# NAVIGATION_-_MCU.net
KiCad netlist of a schematic drawn in Altium Designer
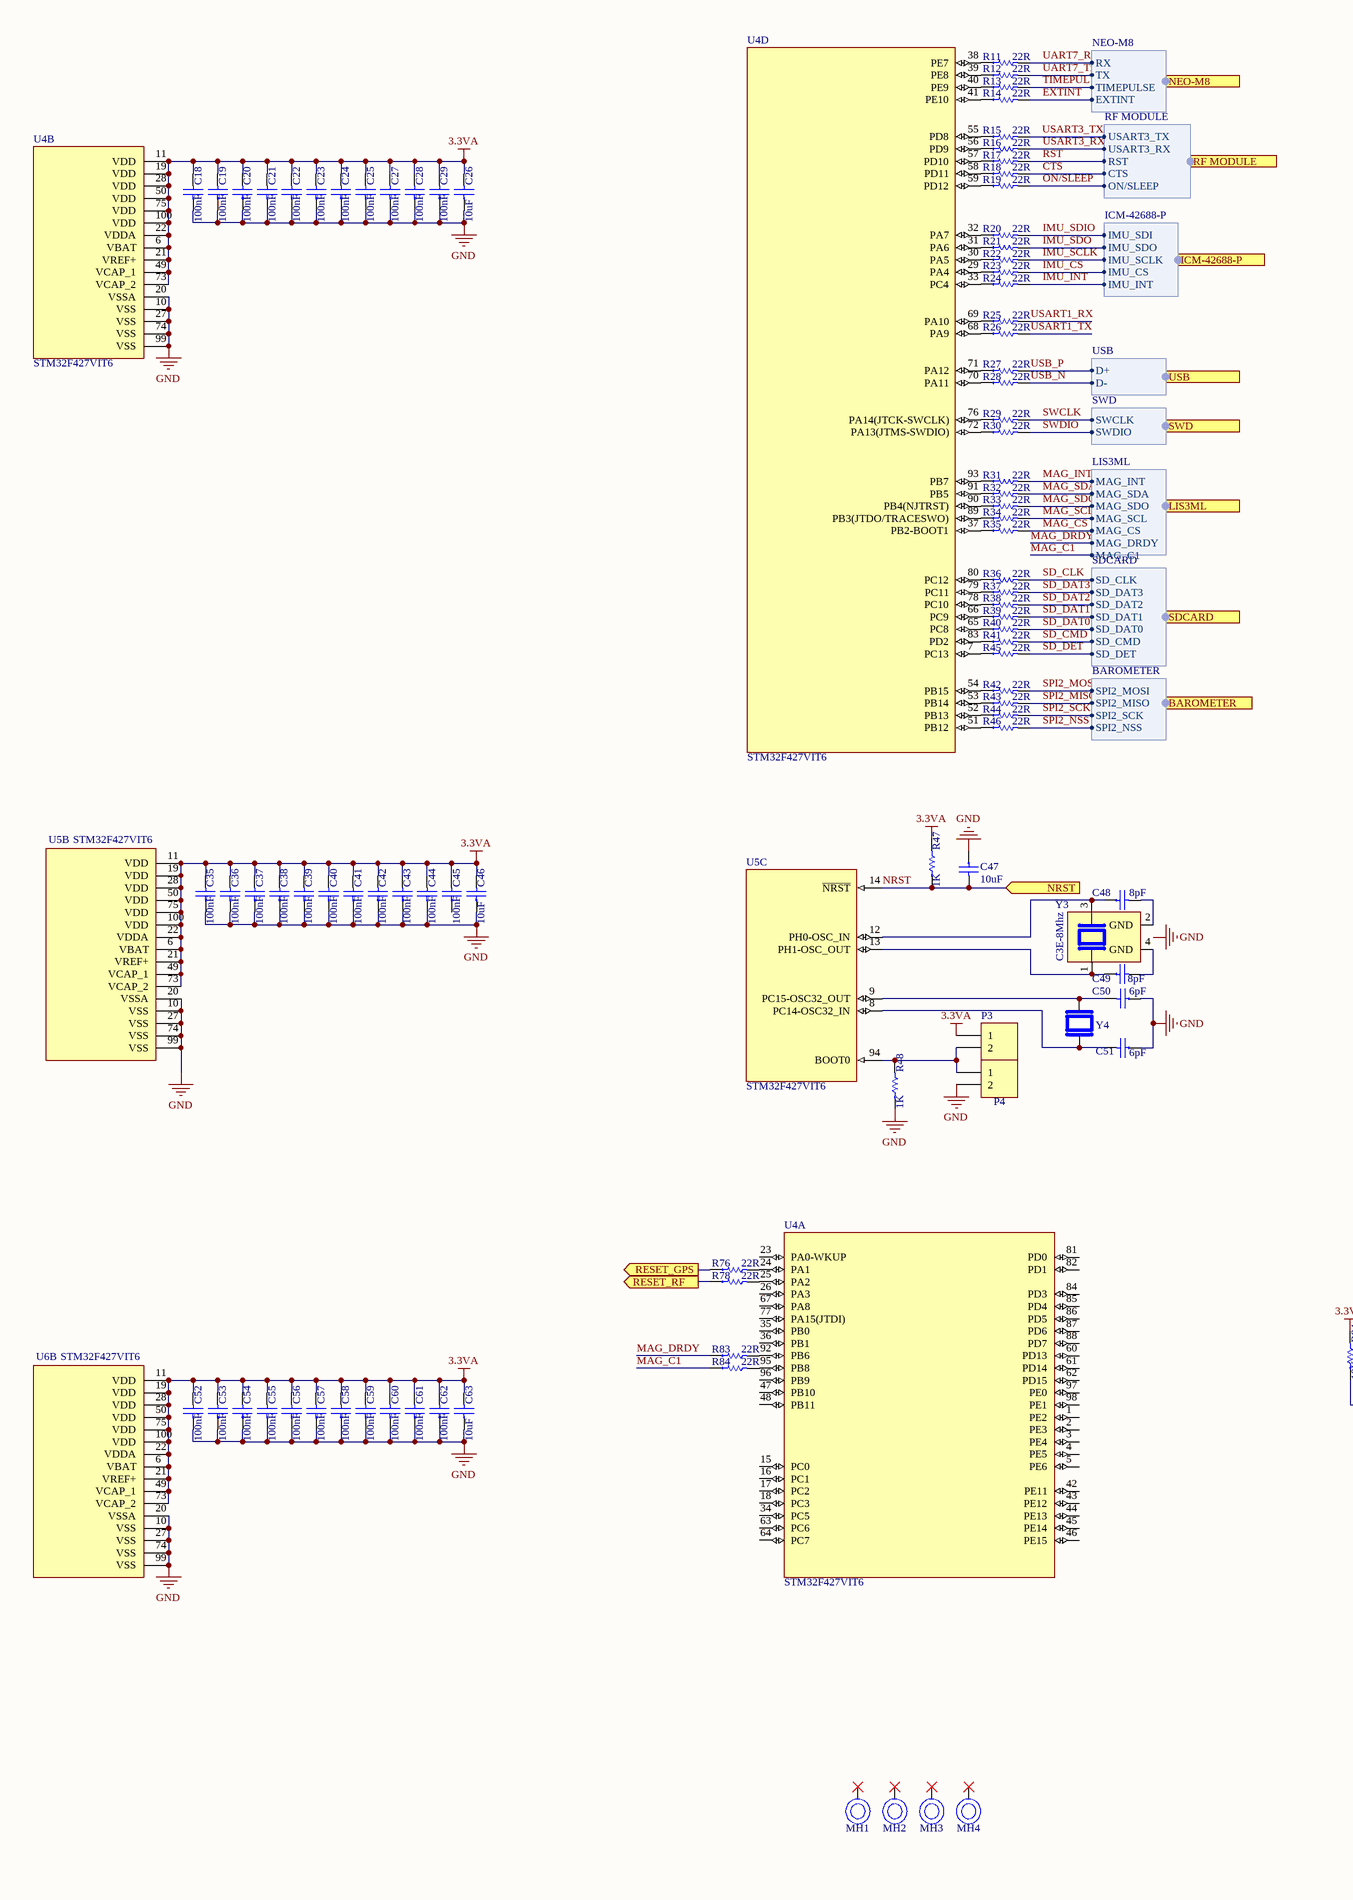
[diagram p0: NAVIGATION - MCU.SchDoc, left]
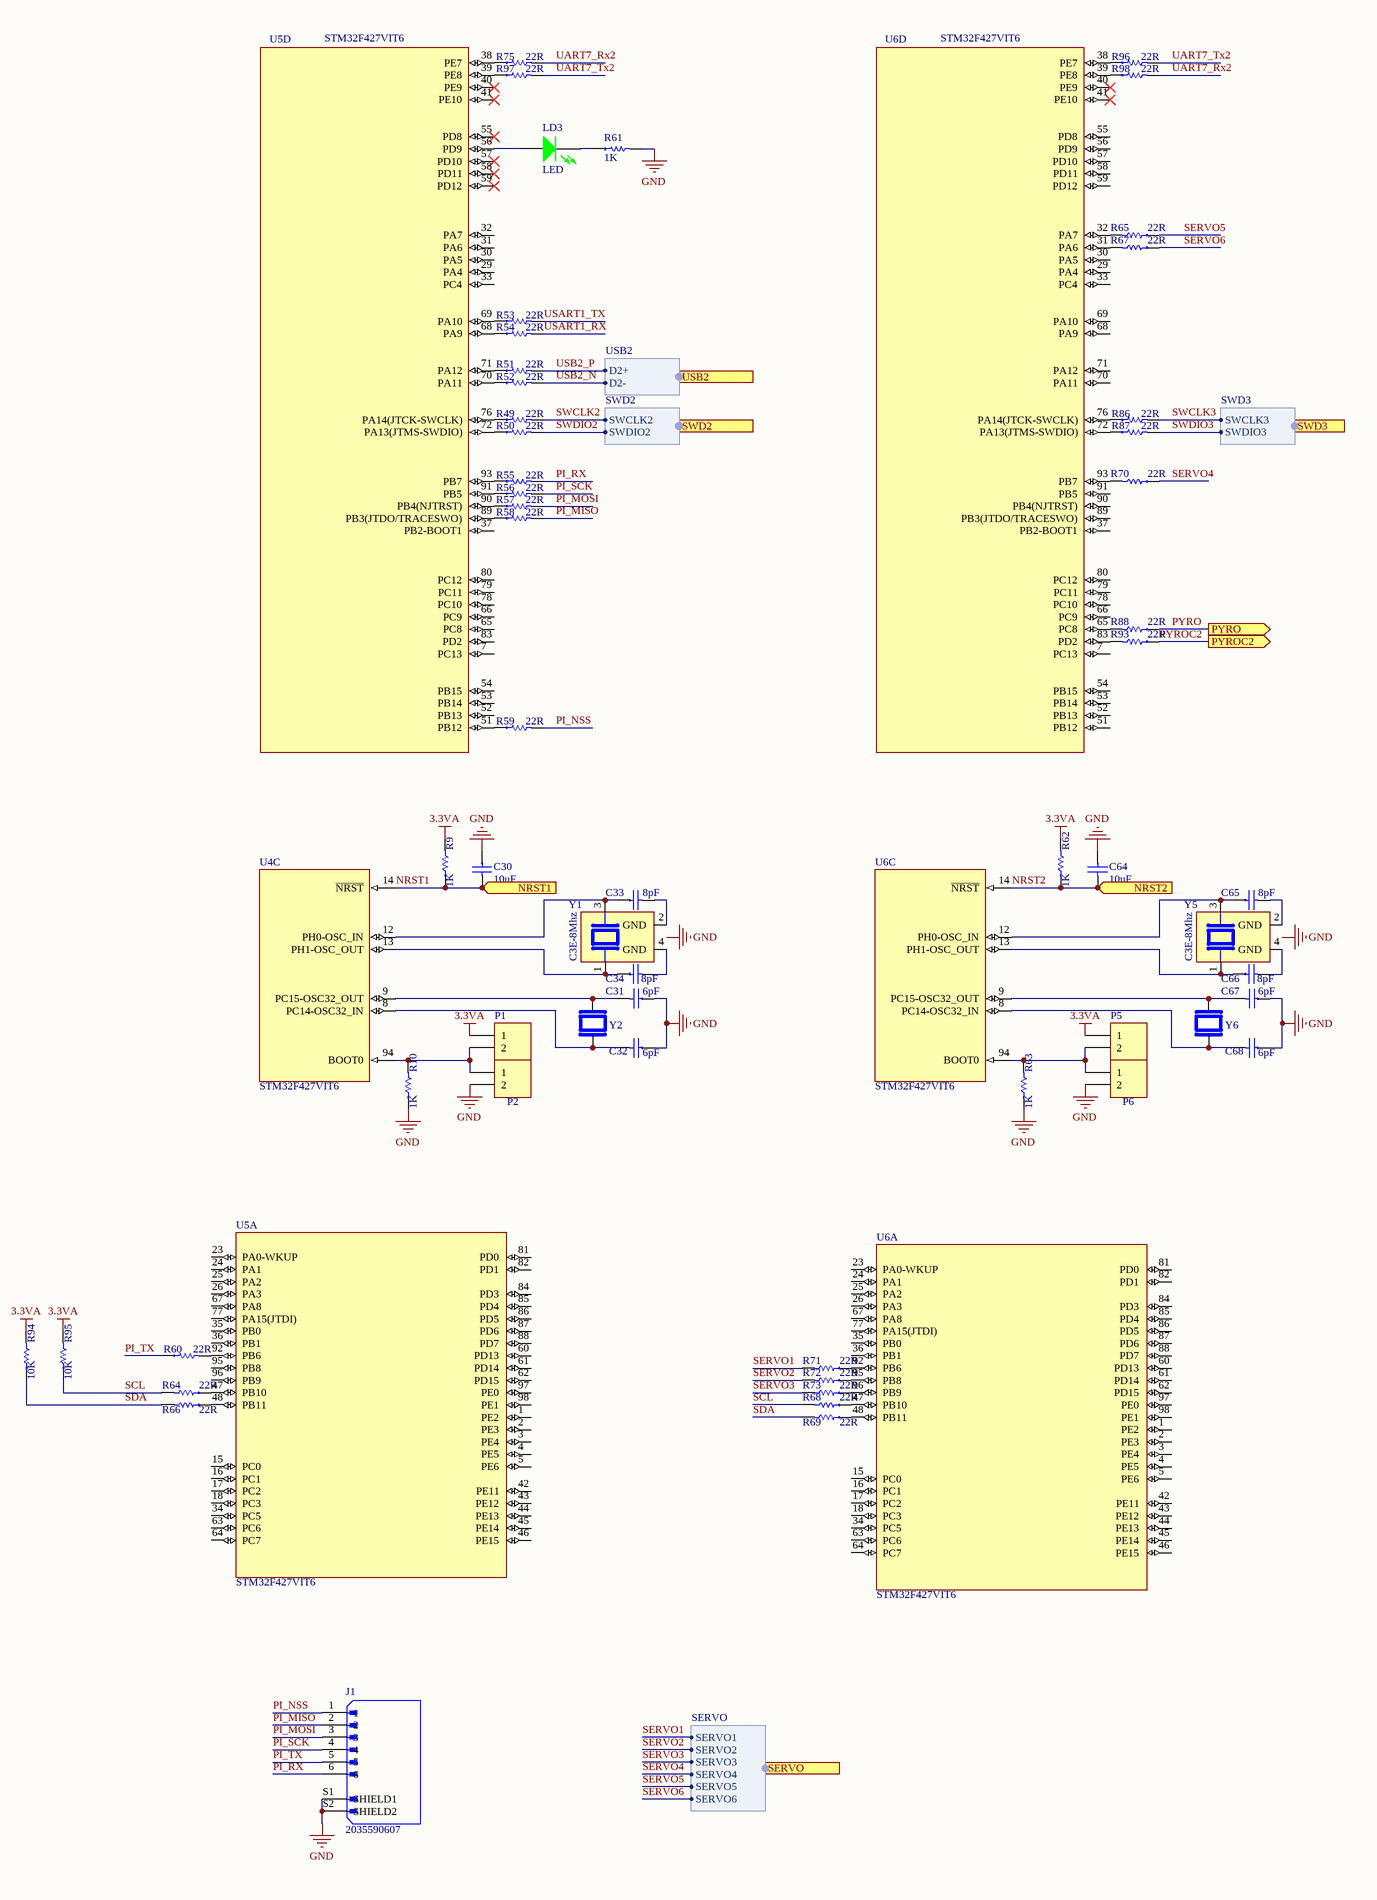
[diagram p1: NAVIGATION - MCU.SchDoc, right]

(export (version "E")
  (design (tool "Eeschema 10.0.6"))
  (components
    (comp (ref "C18")
      (value "100nF")
      (footprint "CAP-CER0402-0.5H")
      (description "CAP CER 100nF 10% 50V X7R 0402 SMD")
      (libsource (lib "2502-GMQLITE-MAIN") (part "CAPCER0013 100nF 10% 50V X7R 0402 SMD"))
    )
    (comp (ref "C19")
      (value "100nF")
      (footprint "CAP-CER0402-0.5H")
      (description "CAP CER 100nF 10% 50V X7R 0402 SMD")
      (libsource (lib "2502-GMQLITE-MAIN") (part "CAPCER0013 100nF 10% 50V X7R 0402 SMD"))
    )
    (comp (ref "C20")
      (value "100nF")
      (footprint "CAP-CER0402-0.5H")
      (description "CAP CER 100nF 10% 50V X7R 0402 SMD")
      (libsource (lib "2502-GMQLITE-MAIN") (part "CAPCER0013 100nF 10% 50V X7R 0402 SMD"))
    )
    (comp (ref "C21")
      (value "100nF")
      (footprint "CAP-CER0402-0.5H")
      (description "CAP CER 100nF 10% 50V X7R 0402 SMD")
      (libsource (lib "2502-GMQLITE-MAIN") (part "CAPCER0013 100nF 10% 50V X7R 0402 SMD"))
    )
    (comp (ref "C22")
      (value "100nF")
      (footprint "CAP-CER0402-0.5H")
      (description "CAP CER 100nF 10% 50V X7R 0402 SMD")
      (libsource (lib "2502-GMQLITE-MAIN") (part "CAPCER0013 100nF 10% 50V X7R 0402 SMD"))
    )
    (comp (ref "C23")
      (value "100nF")
      (footprint "CAP-CER0402-0.5H")
      (description "CAP CER 100nF 10% 50V X7R 0402 SMD")
      (libsource (lib "2502-GMQLITE-MAIN") (part "CAPCER0013 100nF 10% 50V X7R 0402 SMD"))
    )
    (comp (ref "C24")
      (value "100nF")
      (footprint "CAP-CER0402-0.5H")
      (description "CAP CER 100nF 10% 50V X7R 0402 SMD")
      (libsource (lib "2502-GMQLITE-MAIN") (part "CAPCER0013 100nF 10% 50V X7R 0402 SMD"))
    )
    (comp (ref "C25")
      (value "100nF")
      (footprint "CAP-CER0402-0.5H")
      (description "CAP CER 100nF 10% 50V X7R 0402 SMD")
      (libsource (lib "2502-GMQLITE-MAIN") (part "CAPCER0013 100nF 10% 50V X7R 0402 SMD"))
    )
    (comp (ref "C26")
      (value "10uF")
      (footprint "CAP-CER0402-20mil")
      (description "CAP CER 10uF 20% 6.3V X5R 0402 SMD")
      (libsource (lib "2502-GMQLITE-MAIN") (part "CAPCER0040 10uF 20% 6.3V X5R 0402 SMD"))
    )
    (comp (ref "C27")
      (value "100nF")
      (footprint "CAP-CER0402-0.5H")
      (description "CAP CER 100nF 10% 50V X7R 0402 SMD")
      (libsource (lib "2502-GMQLITE-MAIN") (part "CAPCER0013 100nF 10% 50V X7R 0402 SMD"))
    )
    (comp (ref "C28")
      (value "100nF")
      (footprint "CAP-CER0402-0.5H")
      (description "CAP CER 100nF 10% 50V X7R 0402 SMD")
      (libsource (lib "2502-GMQLITE-MAIN") (part "CAPCER0013 100nF 10% 50V X7R 0402 SMD"))
    )
    (comp (ref "C29")
      (value "100nF")
      (footprint "CAP-CER0402-0.5H")
      (description "CAP CER 100nF 10% 50V X7R 0402 SMD")
      (libsource (lib "2502-GMQLITE-MAIN") (part "CAPCER0013 100nF 10% 50V X7R 0402 SMD"))
    )
    (comp (ref "C30")
      (value "10uF")
      (footprint "CAP-CER0402-20mil")
      (description "CAP CER 10uF 20% 6.3V X5R 0402 SMD")
      (libsource (lib "2502-GMQLITE-MAIN") (part "CAPCER0040 10uF 20% 6.3V X5R 0402 SMD"))
    )
    (comp (ref "C31")
      (value "6pF")
      (footprint "CAP-CER0402-0.5H")
      (description "CAP CER 100nF 10% 50V X7R 0402 SMD")
      (libsource (lib "2502-GMQLITE-MAIN") (part "CAPCER0013 100nF 10% 50V X7R 0402 SMD"))
    )
    (comp (ref "C32")
      (value "6pF")
      (footprint "CAP-CER0402-0.5H")
      (description "CAP CER 100nF 10% 50V X7R 0402 SMD")
      (libsource (lib "2502-GMQLITE-MAIN") (part "CAPCER0013 100nF 10% 50V X7R 0402 SMD"))
    )
    (comp (ref "C33")
      (value "8pF")
      (footprint "CAP-CER0402-0.5H")
      (description "CAP CER 100nF 10% 50V X7R 0402 SMD")
      (libsource (lib "2502-GMQLITE-MAIN") (part "CAPCER0013 100nF 10% 50V X7R 0402 SMD"))
    )
    (comp (ref "C34")
      (value "8pF")
      (footprint "CAP-CER0402-0.5H")
      (description "CAP CER 100nF 10% 50V X7R 0402 SMD")
      (libsource (lib "2502-GMQLITE-MAIN") (part "CAPCER0013 100nF 10% 50V X7R 0402 SMD"))
    )
    (comp (ref "C35")
      (value "100nF")
      (footprint "CAP-CER0402-0.5H")
      (description "CAP CER 100nF 10% 50V X7R 0402 SMD")
      (libsource (lib "2502-GMQLITE-MAIN") (part "CAPCER0013 100nF 10% 50V X7R 0402 SMD"))
    )
    (comp (ref "C36")
      (value "100nF")
      (footprint "CAP-CER0402-0.5H")
      (description "CAP CER 100nF 10% 50V X7R 0402 SMD")
      (libsource (lib "2502-GMQLITE-MAIN") (part "CAPCER0013 100nF 10% 50V X7R 0402 SMD"))
    )
    (comp (ref "C37")
      (value "100nF")
      (footprint "CAP-CER0402-0.5H")
      (description "CAP CER 100nF 10% 50V X7R 0402 SMD")
      (libsource (lib "2502-GMQLITE-MAIN") (part "CAPCER0013 100nF 10% 50V X7R 0402 SMD"))
    )
    (comp (ref "C38")
      (value "100nF")
      (footprint "CAP-CER0402-0.5H")
      (description "CAP CER 100nF 10% 50V X7R 0402 SMD")
      (libsource (lib "2502-GMQLITE-MAIN") (part "CAPCER0013 100nF 10% 50V X7R 0402 SMD"))
    )
    (comp (ref "C39")
      (value "100nF")
      (footprint "CAP-CER0402-0.5H")
      (description "CAP CER 100nF 10% 50V X7R 0402 SMD")
      (libsource (lib "2502-GMQLITE-MAIN") (part "CAPCER0013 100nF 10% 50V X7R 0402 SMD"))
    )
    (comp (ref "C40")
      (value "100nF")
      (footprint "CAP-CER0402-0.5H")
      (description "CAP CER 100nF 10% 50V X7R 0402 SMD")
      (libsource (lib "2502-GMQLITE-MAIN") (part "CAPCER0013 100nF 10% 50V X7R 0402 SMD"))
    )
    (comp (ref "C41")
      (value "100nF")
      (footprint "CAP-CER0402-0.5H")
      (description "CAP CER 100nF 10% 50V X7R 0402 SMD")
      (libsource (lib "2502-GMQLITE-MAIN") (part "CAPCER0013 100nF 10% 50V X7R 0402 SMD"))
    )
    (comp (ref "C42")
      (value "100nF")
      (footprint "CAP-CER0402-0.5H")
      (description "CAP CER 100nF 10% 50V X7R 0402 SMD")
      (libsource (lib "2502-GMQLITE-MAIN") (part "CAPCER0013 100nF 10% 50V X7R 0402 SMD"))
    )
    (comp (ref "C43")
      (value "100nF")
      (footprint "CAP-CER0402-0.5H")
      (description "CAP CER 100nF 10% 50V X7R 0402 SMD")
      (libsource (lib "2502-GMQLITE-MAIN") (part "CAPCER0013 100nF 10% 50V X7R 0402 SMD"))
    )
    (comp (ref "C44")
      (value "100nF")
      (footprint "CAP-CER0402-0.5H")
      (description "CAP CER 100nF 10% 50V X7R 0402 SMD")
      (libsource (lib "2502-GMQLITE-MAIN") (part "CAPCER0013 100nF 10% 50V X7R 0402 SMD"))
    )
    (comp (ref "C45")
      (value "100nF")
      (footprint "CAP-CER0402-0.5H")
      (description "CAP CER 100nF 10% 50V X7R 0402 SMD")
      (libsource (lib "2502-GMQLITE-MAIN") (part "CAPCER0013 100nF 10% 50V X7R 0402 SMD"))
    )
    (comp (ref "C46")
      (value "10uF")
      (footprint "CAP-CER0402-20mil")
      (description "CAP CER 10uF 20% 6.3V X5R 0402 SMD")
      (libsource (lib "2502-GMQLITE-MAIN") (part "CAPCER0040 10uF 20% 6.3V X5R 0402 SMD"))
    )
    (comp (ref "C47")
      (value "10uF")
      (footprint "CAP-CER0402-20mil")
      (description "CAP CER 10uF 20% 6.3V X5R 0402 SMD")
      (libsource (lib "2502-GMQLITE-MAIN") (part "CAPCER0040 10uF 20% 6.3V X5R 0402 SMD"))
    )
    (comp (ref "C48")
      (value "8pF")
      (footprint "CAP-CER0402-0.5H")
      (description "CAP CER 100nF 10% 50V X7R 0402 SMD")
      (libsource (lib "2502-GMQLITE-MAIN") (part "CAPCER0013 100nF 10% 50V X7R 0402 SMD"))
    )
    (comp (ref "C49")
      (value "8pF")
      (footprint "CAP-CER0402-0.5H")
      (description "CAP CER 100nF 10% 50V X7R 0402 SMD")
      (libsource (lib "2502-GMQLITE-MAIN") (part "CAPCER0013 100nF 10% 50V X7R 0402 SMD"))
    )
    (comp (ref "C50")
      (value "6pF")
      (footprint "CAP-CER0402-0.5H")
      (description "CAP CER 100nF 10% 50V X7R 0402 SMD")
      (libsource (lib "2502-GMQLITE-MAIN") (part "CAPCER0013 100nF 10% 50V X7R 0402 SMD"))
    )
    (comp (ref "C51")
      (value "6pF")
      (footprint "CAP-CER0402-0.5H")
      (description "CAP CER 100nF 10% 50V X7R 0402 SMD")
      (libsource (lib "2502-GMQLITE-MAIN") (part "CAPCER0013 100nF 10% 50V X7R 0402 SMD"))
    )
    (comp (ref "C52")
      (value "100nF")
      (footprint "CAP-CER0402-0.5H")
      (description "CAP CER 100nF 10% 50V X7R 0402 SMD")
      (libsource (lib "2502-GMQLITE-MAIN") (part "CAPCER0013 100nF 10% 50V X7R 0402 SMD"))
    )
    (comp (ref "C53")
      (value "100nF")
      (footprint "CAP-CER0402-0.5H")
      (description "CAP CER 100nF 10% 50V X7R 0402 SMD")
      (libsource (lib "2502-GMQLITE-MAIN") (part "CAPCER0013 100nF 10% 50V X7R 0402 SMD"))
    )
    (comp (ref "C54")
      (value "100nF")
      (footprint "CAP-CER0402-0.5H")
      (description "CAP CER 100nF 10% 50V X7R 0402 SMD")
      (libsource (lib "2502-GMQLITE-MAIN") (part "CAPCER0013 100nF 10% 50V X7R 0402 SMD"))
    )
    (comp (ref "C55")
      (value "100nF")
      (footprint "CAP-CER0402-0.5H")
      (description "CAP CER 100nF 10% 50V X7R 0402 SMD")
      (libsource (lib "2502-GMQLITE-MAIN") (part "CAPCER0013 100nF 10% 50V X7R 0402 SMD"))
    )
    (comp (ref "C56")
      (value "100nF")
      (footprint "CAP-CER0402-0.5H")
      (description "CAP CER 100nF 10% 50V X7R 0402 SMD")
      (libsource (lib "2502-GMQLITE-MAIN") (part "CAPCER0013 100nF 10% 50V X7R 0402 SMD"))
    )
    (comp (ref "C57")
      (value "100nF")
      (footprint "CAP-CER0402-0.5H")
      (description "CAP CER 100nF 10% 50V X7R 0402 SMD")
      (libsource (lib "2502-GMQLITE-MAIN") (part "CAPCER0013 100nF 10% 50V X7R 0402 SMD"))
    )
    (comp (ref "C58")
      (value "100nF")
      (footprint "CAP-CER0402-0.5H")
      (description "CAP CER 100nF 10% 50V X7R 0402 SMD")
      (libsource (lib "2502-GMQLITE-MAIN") (part "CAPCER0013 100nF 10% 50V X7R 0402 SMD"))
    )
    (comp (ref "C59")
      (value "100nF")
      (footprint "CAP-CER0402-0.5H")
      (description "CAP CER 100nF 10% 50V X7R 0402 SMD")
      (libsource (lib "2502-GMQLITE-MAIN") (part "CAPCER0013 100nF 10% 50V X7R 0402 SMD"))
    )
    (comp (ref "C60")
      (value "100nF")
      (footprint "CAP-CER0402-0.5H")
      (description "CAP CER 100nF 10% 50V X7R 0402 SMD")
      (libsource (lib "2502-GMQLITE-MAIN") (part "CAPCER0013 100nF 10% 50V X7R 0402 SMD"))
    )
    (comp (ref "C61")
      (value "100nF")
      (footprint "CAP-CER0402-0.5H")
      (description "CAP CER 100nF 10% 50V X7R 0402 SMD")
      (libsource (lib "2502-GMQLITE-MAIN") (part "CAPCER0013 100nF 10% 50V X7R 0402 SMD"))
    )
    (comp (ref "C62")
      (value "100nF")
      (footprint "CAP-CER0402-0.5H")
      (description "CAP CER 100nF 10% 50V X7R 0402 SMD")
      (libsource (lib "2502-GMQLITE-MAIN") (part "CAPCER0013 100nF 10% 50V X7R 0402 SMD"))
    )
    (comp (ref "C63")
      (value "10uF")
      (footprint "CAP-CER0402-20mil")
      (description "CAP CER 10uF 20% 6.3V X5R 0402 SMD")
      (libsource (lib "2502-GMQLITE-MAIN") (part "CAPCER0040 10uF 20% 6.3V X5R 0402 SMD"))
    )
    (comp (ref "C64")
      (value "10uF")
      (footprint "CAP-CER0402-20mil")
      (description "CAP CER 10uF 20% 6.3V X5R 0402 SMD")
      (libsource (lib "2502-GMQLITE-MAIN") (part "CAPCER0040 10uF 20% 6.3V X5R 0402 SMD"))
    )
    (comp (ref "C65")
      (value "8pF")
      (footprint "CAP-CER0402-0.5H")
      (description "CAP CER 100nF 10% 50V X7R 0402 SMD")
      (libsource (lib "2502-GMQLITE-MAIN") (part "CAPCER0013 100nF 10% 50V X7R 0402 SMD"))
    )
    (comp (ref "C66")
      (value "8pF")
      (footprint "CAP-CER0402-0.5H")
      (description "CAP CER 100nF 10% 50V X7R 0402 SMD")
      (libsource (lib "2502-GMQLITE-MAIN") (part "CAPCER0013 100nF 10% 50V X7R 0402 SMD"))
    )
    (comp (ref "C67")
      (value "6pF")
      (footprint "CAP-CER0402-0.5H")
      (description "CAP CER 100nF 10% 50V X7R 0402 SMD")
      (libsource (lib "2502-GMQLITE-MAIN") (part "CAPCER0013 100nF 10% 50V X7R 0402 SMD"))
    )
    (comp (ref "C68")
      (value "6pF")
      (footprint "CAP-CER0402-0.5H")
      (description "CAP CER 100nF 10% 50V X7R 0402 SMD")
      (libsource (lib "2502-GMQLITE-MAIN") (part "CAPCER0013 100nF 10% 50V X7R 0402 SMD"))
    )
    (comp (ref "J1")
      (value "2035590607")
      (footprint "MOLEX_2035590607")
      (libsource (lib "2035590607") (part "2035590607"))
    )
    (comp (ref "LD3")
      (value "LED")
      (footprint "LED-IND0402-GRE-0.4H")
      (description "LED IND GRE CLR 2.4V 20mA 0402 SMD")
      (libsource (lib "2502-GMQLITE-MAIN") (part "LEDIND0005 GRE CLR 2.4V 20mA 0402 SMD"))
    )
    (comp (ref "MH1") (value "MOUNTING HOLE") (footprint "M3") (libsource (lib "INVERTER") (part "MH")))
    (comp (ref "MH2") (value "MOUNTING HOLE") (footprint "M3") (libsource (lib "INVERTER") (part "MH")))
    (comp (ref "MH3") (value "MOUNTING HOLE") (footprint "M3") (libsource (lib "INVERTER") (part "MH")))
    (comp (ref "MH4") (value "MOUNTING HOLE") (footprint "M3") (libsource (lib "INVERTER") (part "MH")))
    (comp (ref "P1")
      (value "Header 2")
      (footprint "HDR1X2")
      (description "Header, 2-Pin")
      (fields (field (name "PUBLISHER") "Altium Limited"))
      (libsource (lib "PIKVM-PI4-0925") (part "Header 2"))
    )
    (comp (ref "P2")
      (value "Header 2")
      (footprint "HDR1X2")
      (description "Header, 2-Pin")
      (fields (field (name "PUBLISHER") "Altium Limited"))
      (libsource (lib "PIKVM-PI4-0925") (part "Header 2"))
    )
    (comp (ref "P3")
      (value "Header 2")
      (footprint "HDR1X2")
      (description "Header, 2-Pin")
      (fields (field (name "PUBLISHER") "Altium Limited"))
      (libsource (lib "PIKVM-PI4-0925") (part "Header 2"))
    )
    (comp (ref "P4")
      (value "Header 2")
      (footprint "HDR1X2")
      (description "Header, 2-Pin")
      (fields (field (name "PUBLISHER") "Altium Limited"))
      (libsource (lib "PIKVM-PI4-0925") (part "Header 2"))
    )
    (comp (ref "P5")
      (value "Header 2")
      (footprint "HDR1X2")
      (description "Header, 2-Pin")
      (fields (field (name "PUBLISHER") "Altium Limited"))
      (libsource (lib "PIKVM-PI4-0925") (part "Header 2"))
    )
    (comp (ref "P6")
      (value "Header 2")
      (footprint "HDR1X2")
      (description "Header, 2-Pin")
      (fields (field (name "PUBLISHER") "Altium Limited"))
      (libsource (lib "PIKVM-PI4-0925") (part "Header 2"))
    )
    (comp (ref "R9")
      (value "1K")
      (footprint "RES-CHP0402-0.35H")
      (description "RES CHP 100K 1% 1/16W 0402 SMD")
      (libsource (lib "2502-GMQLITE-MAIN") (part "RESCHP0097 100K 1% 0402 SMD"))
    )
    (comp (ref "R10")
      (value "1K")
      (footprint "RES-CHP0402-0.35H")
      (description "RES CHP 100K 1% 1/16W 0402 SMD")
      (libsource (lib "2502-GMQLITE-MAIN") (part "RESCHP0097 100K 1% 0402 SMD"))
    )
    (comp (ref "R11")
      (value "22R")
      (footprint "RES-CHP0402-0.35H")
      (description "RES CHP 100K 1% 1/16W 0402 SMD")
      (libsource (lib "2502-GMQLITE-MAIN") (part "RESCHP0097 100K 1% 0402 SMD"))
    )
    (comp (ref "R12")
      (value "22R")
      (footprint "RES-CHP0402-0.35H")
      (description "RES CHP 100K 1% 1/16W 0402 SMD")
      (libsource (lib "2502-GMQLITE-MAIN") (part "RESCHP0097 100K 1% 0402 SMD"))
    )
    (comp (ref "R13")
      (value "22R")
      (footprint "RES-CHP0402-0.35H")
      (description "RES CHP 100K 1% 1/16W 0402 SMD")
      (libsource (lib "2502-GMQLITE-MAIN") (part "RESCHP0097 100K 1% 0402 SMD"))
    )
    (comp (ref "R14")
      (value "22R")
      (footprint "RES-CHP0402-0.35H")
      (description "RES CHP 100K 1% 1/16W 0402 SMD")
      (libsource (lib "2502-GMQLITE-MAIN") (part "RESCHP0097 100K 1% 0402 SMD"))
    )
    (comp (ref "R15")
      (value "22R")
      (footprint "RES-CHP0402-0.35H")
      (description "RES CHP 100K 1% 1/16W 0402 SMD")
      (libsource (lib "2502-GMQLITE-MAIN") (part "RESCHP0097 100K 1% 0402 SMD"))
    )
    (comp (ref "R16")
      (value "22R")
      (footprint "RES-CHP0402-0.35H")
      (description "RES CHP 100K 1% 1/16W 0402 SMD")
      (libsource (lib "2502-GMQLITE-MAIN") (part "RESCHP0097 100K 1% 0402 SMD"))
    )
    (comp (ref "R17")
      (value "22R")
      (footprint "RES-CHP0402-0.35H")
      (description "RES CHP 100K 1% 1/16W 0402 SMD")
      (libsource (lib "2502-GMQLITE-MAIN") (part "RESCHP0097 100K 1% 0402 SMD"))
    )
    (comp (ref "R18")
      (value "22R")
      (footprint "RES-CHP0402-0.35H")
      (description "RES CHP 100K 1% 1/16W 0402 SMD")
      (libsource (lib "2502-GMQLITE-MAIN") (part "RESCHP0097 100K 1% 0402 SMD"))
    )
    (comp (ref "R19")
      (value "22R")
      (footprint "RES-CHP0402-0.35H")
      (description "RES CHP 100K 1% 1/16W 0402 SMD")
      (libsource (lib "2502-GMQLITE-MAIN") (part "RESCHP0097 100K 1% 0402 SMD"))
    )
    (comp (ref "R20")
      (value "22R")
      (footprint "RES-CHP0402-0.35H")
      (description "RES CHP 100K 1% 1/16W 0402 SMD")
      (libsource (lib "2502-GMQLITE-MAIN") (part "RESCHP0097 100K 1% 0402 SMD"))
    )
    (comp (ref "R21")
      (value "22R")
      (footprint "RES-CHP0402-0.35H")
      (description "RES CHP 100K 1% 1/16W 0402 SMD")
      (libsource (lib "2502-GMQLITE-MAIN") (part "RESCHP0097 100K 1% 0402 SMD"))
    )
    (comp (ref "R22")
      (value "22R")
      (footprint "RES-CHP0402-0.35H")
      (description "RES CHP 100K 1% 1/16W 0402 SMD")
      (libsource (lib "2502-GMQLITE-MAIN") (part "RESCHP0097 100K 1% 0402 SMD"))
    )
    (comp (ref "R23")
      (value "22R")
      (footprint "RES-CHP0402-0.35H")
      (description "RES CHP 100K 1% 1/16W 0402 SMD")
      (libsource (lib "2502-GMQLITE-MAIN") (part "RESCHP0097 100K 1% 0402 SMD"))
    )
    (comp (ref "R24")
      (value "22R")
      (footprint "RES-CHP0402-0.35H")
      (description "RES CHP 100K 1% 1/16W 0402 SMD")
      (libsource (lib "2502-GMQLITE-MAIN") (part "RESCHP0097 100K 1% 0402 SMD"))
    )
    (comp (ref "R25")
      (value "22R")
      (footprint "RES-CHP0402-0.35H")
      (description "RES CHP 100K 1% 1/16W 0402 SMD")
      (libsource (lib "2502-GMQLITE-MAIN") (part "RESCHP0097 100K 1% 0402 SMD"))
    )
    (comp (ref "R26")
      (value "22R")
      (footprint "RES-CHP0402-0.35H")
      (description "RES CHP 100K 1% 1/16W 0402 SMD")
      (libsource (lib "2502-GMQLITE-MAIN") (part "RESCHP0097 100K 1% 0402 SMD"))
    )
    (comp (ref "R27")
      (value "22R")
      (footprint "RES-CHP0402-0.35H")
      (description "RES CHP 100K 1% 1/16W 0402 SMD")
      (libsource (lib "2502-GMQLITE-MAIN") (part "RESCHP0097 100K 1% 0402 SMD"))
    )
    (comp (ref "R28")
      (value "22R")
      (footprint "RES-CHP0402-0.35H")
      (description "RES CHP 100K 1% 1/16W 0402 SMD")
      (libsource (lib "2502-GMQLITE-MAIN") (part "RESCHP0097 100K 1% 0402 SMD"))
    )
    (comp (ref "R29")
      (value "22R")
      (footprint "RES-CHP0402-0.35H")
      (description "RES CHP 100K 1% 1/16W 0402 SMD")
      (libsource (lib "2502-GMQLITE-MAIN") (part "RESCHP0097 100K 1% 0402 SMD"))
    )
    (comp (ref "R30")
      (value "22R")
      (footprint "RES-CHP0402-0.35H")
      (description "RES CHP 100K 1% 1/16W 0402 SMD")
      (libsource (lib "2502-GMQLITE-MAIN") (part "RESCHP0097 100K 1% 0402 SMD"))
    )
    (comp (ref "R31")
      (value "22R")
      (footprint "RES-CHP0402-0.35H")
      (description "RES CHP 100K 1% 1/16W 0402 SMD")
      (libsource (lib "2502-GMQLITE-MAIN") (part "RESCHP0097 100K 1% 0402 SMD"))
    )
    (comp (ref "R32")
      (value "22R")
      (footprint "RES-CHP0402-0.35H")
      (description "RES CHP 100K 1% 1/16W 0402 SMD")
      (libsource (lib "2502-GMQLITE-MAIN") (part "RESCHP0097 100K 1% 0402 SMD"))
    )
    (comp (ref "R33")
      (value "22R")
      (footprint "RES-CHP0402-0.35H")
      (description "RES CHP 100K 1% 1/16W 0402 SMD")
      (libsource (lib "2502-GMQLITE-MAIN") (part "RESCHP0097 100K 1% 0402 SMD"))
    )
    (comp (ref "R34")
      (value "22R")
      (footprint "RES-CHP0402-0.35H")
      (description "RES CHP 100K 1% 1/16W 0402 SMD")
      (libsource (lib "2502-GMQLITE-MAIN") (part "RESCHP0097 100K 1% 0402 SMD"))
    )
    (comp (ref "R35")
      (value "22R")
      (footprint "RES-CHP0402-0.35H")
      (description "RES CHP 100K 1% 1/16W 0402 SMD")
      (libsource (lib "2502-GMQLITE-MAIN") (part "RESCHP0097 100K 1% 0402 SMD"))
    )
    (comp (ref "R36")
      (value "22R")
      (footprint "RES-CHP0402-0.35H")
      (description "RES CHP 100K 1% 1/16W 0402 SMD")
      (libsource (lib "2502-GMQLITE-MAIN") (part "RESCHP0097 100K 1% 0402 SMD"))
    )
    (comp (ref "R37")
      (value "22R")
      (footprint "RES-CHP0402-0.35H")
      (description "RES CHP 100K 1% 1/16W 0402 SMD")
      (libsource (lib "2502-GMQLITE-MAIN") (part "RESCHP0097 100K 1% 0402 SMD"))
    )
    (comp (ref "R38")
      (value "22R")
      (footprint "RES-CHP0402-0.35H")
      (description "RES CHP 100K 1% 1/16W 0402 SMD")
      (libsource (lib "2502-GMQLITE-MAIN") (part "RESCHP0097 100K 1% 0402 SMD"))
    )
    (comp (ref "R39")
      (value "22R")
      (footprint "RES-CHP0402-0.35H")
      (description "RES CHP 100K 1% 1/16W 0402 SMD")
      (libsource (lib "2502-GMQLITE-MAIN") (part "RESCHP0097 100K 1% 0402 SMD"))
    )
    (comp (ref "R40")
      (value "22R")
      (footprint "RES-CHP0402-0.35H")
      (description "RES CHP 100K 1% 1/16W 0402 SMD")
      (libsource (lib "2502-GMQLITE-MAIN") (part "RESCHP0097 100K 1% 0402 SMD"))
    )
    (comp (ref "R41")
      (value "22R")
      (footprint "RES-CHP0402-0.35H")
      (description "RES CHP 100K 1% 1/16W 0402 SMD")
      (libsource (lib "2502-GMQLITE-MAIN") (part "RESCHP0097 100K 1% 0402 SMD"))
    )
    (comp (ref "R42")
      (value "22R")
      (footprint "RES-CHP0402-0.35H")
      (description "RES CHP 100K 1% 1/16W 0402 SMD")
      (libsource (lib "2502-GMQLITE-MAIN") (part "RESCHP0097 100K 1% 0402 SMD"))
    )
    (comp (ref "R43")
      (value "22R")
      (footprint "RES-CHP0402-0.35H")
      (description "RES CHP 100K 1% 1/16W 0402 SMD")
      (libsource (lib "2502-GMQLITE-MAIN") (part "RESCHP0097 100K 1% 0402 SMD"))
    )
    (comp (ref "R44")
      (value "22R")
      (footprint "RES-CHP0402-0.35H")
      (description "RES CHP 100K 1% 1/16W 0402 SMD")
      (libsource (lib "2502-GMQLITE-MAIN") (part "RESCHP0097 100K 1% 0402 SMD"))
    )
    (comp (ref "R45")
      (value "22R")
      (footprint "RES-CHP0402-0.35H")
      (description "RES CHP 100K 1% 1/16W 0402 SMD")
      (libsource (lib "2502-GMQLITE-MAIN") (part "RESCHP0097 100K 1% 0402 SMD"))
    )
    (comp (ref "R46")
      (value "22R")
      (footprint "RES-CHP0402-0.35H")
      (description "RES CHP 100K 1% 1/16W 0402 SMD")
      (libsource (lib "2502-GMQLITE-MAIN") (part "RESCHP0097 100K 1% 0402 SMD"))
    )
    (comp (ref "R47")
      (value "1K")
      (footprint "RES-CHP0402-0.35H")
      (description "RES CHP 100K 1% 1/16W 0402 SMD")
      (libsource (lib "2502-GMQLITE-MAIN") (part "RESCHP0097 100K 1% 0402 SMD"))
    )
    (comp (ref "R48")
      (value "1K")
      (footprint "RES-CHP0402-0.35H")
      (description "RES CHP 100K 1% 1/16W 0402 SMD")
      (libsource (lib "2502-GMQLITE-MAIN") (part "RESCHP0097 100K 1% 0402 SMD"))
    )
    (comp (ref "R49")
      (value "22R")
      (footprint "RES-CHP0402-0.35H")
      (description "RES CHP 100K 1% 1/16W 0402 SMD")
      (libsource (lib "2502-GMQLITE-MAIN") (part "RESCHP0097 100K 1% 0402 SMD"))
    )
    (comp (ref "R50")
      (value "22R")
      (footprint "RES-CHP0402-0.35H")
      (description "RES CHP 100K 1% 1/16W 0402 SMD")
      (libsource (lib "2502-GMQLITE-MAIN") (part "RESCHP0097 100K 1% 0402 SMD"))
    )
    (comp (ref "R51")
      (value "22R")
      (footprint "RES-CHP0402-0.35H")
      (description "RES CHP 100K 1% 1/16W 0402 SMD")
      (libsource (lib "2502-GMQLITE-MAIN") (part "RESCHP0097 100K 1% 0402 SMD"))
    )
    (comp (ref "R52")
      (value "22R")
      (footprint "RES-CHP0402-0.35H")
      (description "RES CHP 100K 1% 1/16W 0402 SMD")
      (libsource (lib "2502-GMQLITE-MAIN") (part "RESCHP0097 100K 1% 0402 SMD"))
    )
    (comp (ref "R53")
      (value "22R")
      (footprint "RES-CHP0402-0.35H")
      (description "RES CHP 100K 1% 1/16W 0402 SMD")
      (libsource (lib "2502-GMQLITE-MAIN") (part "RESCHP0097 100K 1% 0402 SMD"))
    )
    (comp (ref "R54")
      (value "22R")
      (footprint "RES-CHP0402-0.35H")
      (description "RES CHP 100K 1% 1/16W 0402 SMD")
      (libsource (lib "2502-GMQLITE-MAIN") (part "RESCHP0097 100K 1% 0402 SMD"))
    )
    (comp (ref "R55")
      (value "22R")
      (footprint "RES-CHP0402-0.35H")
      (description "RES CHP 100K 1% 1/16W 0402 SMD")
      (libsource (lib "2502-GMQLITE-MAIN") (part "RESCHP0097 100K 1% 0402 SMD"))
    )
    (comp (ref "R56")
      (value "22R")
      (footprint "RES-CHP0402-0.35H")
      (description "RES CHP 100K 1% 1/16W 0402 SMD")
      (libsource (lib "2502-GMQLITE-MAIN") (part "RESCHP0097 100K 1% 0402 SMD"))
    )
    (comp (ref "R57")
      (value "22R")
      (footprint "RES-CHP0402-0.35H")
      (description "RES CHP 100K 1% 1/16W 0402 SMD")
      (libsource (lib "2502-GMQLITE-MAIN") (part "RESCHP0097 100K 1% 0402 SMD"))
    )
    (comp (ref "R58")
      (value "22R")
      (footprint "RES-CHP0402-0.35H")
      (description "RES CHP 100K 1% 1/16W 0402 SMD")
      (libsource (lib "2502-GMQLITE-MAIN") (part "RESCHP0097 100K 1% 0402 SMD"))
    )
    (comp (ref "R59")
      (value "22R")
      (footprint "RES-CHP0402-0.35H")
      (description "RES CHP 100K 1% 1/16W 0402 SMD")
      (libsource (lib "2502-GMQLITE-MAIN") (part "RESCHP0097 100K 1% 0402 SMD"))
    )
    (comp (ref "R60")
      (value "22R")
      (footprint "RES-CHP0402-0.35H")
      (description "RES CHP 100K 1% 1/16W 0402 SMD")
      (libsource (lib "2502-GMQLITE-MAIN") (part "RESCHP0097 100K 1% 0402 SMD"))
    )
    (comp (ref "R61")
      (value "1K")
      (footprint "RES-CHP0402-0.35H")
      (description "RES CHP 100K 1% 1/16W 0402 SMD")
      (libsource (lib "2502-GMQLITE-MAIN") (part "RESCHP0097 100K 1% 0402 SMD"))
    )
    (comp (ref "R62")
      (value "1K")
      (footprint "RES-CHP0402-0.35H")
      (description "RES CHP 100K 1% 1/16W 0402 SMD")
      (libsource (lib "2502-GMQLITE-MAIN") (part "RESCHP0097 100K 1% 0402 SMD"))
    )
    (comp (ref "R63")
      (value "1K")
      (footprint "RES-CHP0402-0.35H")
      (description "RES CHP 100K 1% 1/16W 0402 SMD")
      (libsource (lib "2502-GMQLITE-MAIN") (part "RESCHP0097 100K 1% 0402 SMD"))
    )
    (comp (ref "R64")
      (value "22R")
      (footprint "RES-CHP0402-0.35H")
      (description "RES CHP 100K 1% 1/16W 0402 SMD")
      (libsource (lib "2502-GMQLITE-MAIN") (part "RESCHP0097 100K 1% 0402 SMD"))
    )
    (comp (ref "R65")
      (value "22R")
      (footprint "RES-CHP0402-0.35H")
      (description "RES CHP 100K 1% 1/16W 0402 SMD")
      (libsource (lib "2502-GMQLITE-MAIN") (part "RESCHP0097 100K 1% 0402 SMD"))
    )
    (comp (ref "R66")
      (value "22R")
      (footprint "RES-CHP0402-0.35H")
      (description "RES CHP 100K 1% 1/16W 0402 SMD")
      (libsource (lib "2502-GMQLITE-MAIN") (part "RESCHP0097 100K 1% 0402 SMD"))
    )
    (comp (ref "R67")
      (value "22R")
      (footprint "RES-CHP0402-0.35H")
      (description "RES CHP 100K 1% 1/16W 0402 SMD")
      (libsource (lib "2502-GMQLITE-MAIN") (part "RESCHP0097 100K 1% 0402 SMD"))
    )
    (comp (ref "R68")
      (value "22R")
      (footprint "RES-CHP0402-0.35H")
      (description "RES CHP 100K 1% 1/16W 0402 SMD")
      (libsource (lib "2502-GMQLITE-MAIN") (part "RESCHP0097 100K 1% 0402 SMD"))
    )
    (comp (ref "R69")
      (value "22R")
      (footprint "RES-CHP0402-0.35H")
      (description "RES CHP 100K 1% 1/16W 0402 SMD")
      (libsource (lib "2502-GMQLITE-MAIN") (part "RESCHP0097 100K 1% 0402 SMD"))
    )
    (comp (ref "R70")
      (value "22R")
      (footprint "RES-CHP0402-0.35H")
      (description "RES CHP 100K 1% 1/16W 0402 SMD")
      (libsource (lib "2502-GMQLITE-MAIN") (part "RESCHP0097 100K 1% 0402 SMD"))
    )
    (comp (ref "R71")
      (value "22R")
      (footprint "RES-CHP0402-0.35H")
      (description "RES CHP 100K 1% 1/16W 0402 SMD")
      (libsource (lib "2502-GMQLITE-MAIN") (part "RESCHP0097 100K 1% 0402 SMD"))
    )
    (comp (ref "R72")
      (value "22R")
      (footprint "RES-CHP0402-0.35H")
      (description "RES CHP 100K 1% 1/16W 0402 SMD")
      (libsource (lib "2502-GMQLITE-MAIN") (part "RESCHP0097 100K 1% 0402 SMD"))
    )
    (comp (ref "R73")
      (value "22R")
      (footprint "RES-CHP0402-0.35H")
      (description "RES CHP 100K 1% 1/16W 0402 SMD")
      (libsource (lib "2502-GMQLITE-MAIN") (part "RESCHP0097 100K 1% 0402 SMD"))
    )
    (comp (ref "R75")
      (value "22R")
      (footprint "RES-CHP0402-0.35H")
      (description "RES CHP 100K 1% 1/16W 0402 SMD")
      (libsource (lib "2502-GMQLITE-MAIN") (part "RESCHP0097 100K 1% 0402 SMD"))
    )
    (comp (ref "R76")
      (value "22R")
      (footprint "RES-CHP0402-0.35H")
      (description "RES CHP 100K 1% 1/16W 0402 SMD")
      (libsource (lib "2502-GMQLITE-MAIN") (part "RESCHP0097 100K 1% 0402 SMD"))
    )
    (comp (ref "R78")
      (value "22R")
      (footprint "RES-CHP0402-0.35H")
      (description "RES CHP 100K 1% 1/16W 0402 SMD")
      (libsource (lib "2502-GMQLITE-MAIN") (part "RESCHP0097 100K 1% 0402 SMD"))
    )
    (comp (ref "R83")
      (value "22R")
      (footprint "RES-CHP0402-0.35H")
      (description "RES CHP 100K 1% 1/16W 0402 SMD")
      (libsource (lib "2502-GMQLITE-MAIN") (part "RESCHP0097 100K 1% 0402 SMD"))
    )
    (comp (ref "R84")
      (value "22R")
      (footprint "RES-CHP0402-0.35H")
      (description "RES CHP 100K 1% 1/16W 0402 SMD")
      (libsource (lib "2502-GMQLITE-MAIN") (part "RESCHP0097 100K 1% 0402 SMD"))
    )
    (comp (ref "R86")
      (value "22R")
      (footprint "RES-CHP0402-0.35H")
      (description "RES CHP 100K 1% 1/16W 0402 SMD")
      (libsource (lib "2502-GMQLITE-MAIN") (part "RESCHP0097 100K 1% 0402 SMD"))
    )
    (comp (ref "R87")
      (value "22R")
      (footprint "RES-CHP0402-0.35H")
      (description "RES CHP 100K 1% 1/16W 0402 SMD")
      (libsource (lib "2502-GMQLITE-MAIN") (part "RESCHP0097 100K 1% 0402 SMD"))
    )
    (comp (ref "R88")
      (value "22R")
      (footprint "RES-CHP0402-0.35H")
      (description "RES CHP 100K 1% 1/16W 0402 SMD")
      (libsource (lib "2502-GMQLITE-MAIN") (part "RESCHP0097 100K 1% 0402 SMD"))
    )
    (comp (ref "R93")
      (value "22R")
      (footprint "RES-CHP0402-0.35H")
      (description "RES CHP 100K 1% 1/16W 0402 SMD")
      (libsource (lib "2502-GMQLITE-MAIN") (part "RESCHP0097 100K 1% 0402 SMD"))
    )
    (comp (ref "R94")
      (value "10K")
      (footprint "RES-CHP0402-0.35H")
      (description "RES CHP 100K 1% 1/16W 0402 SMD")
      (libsource (lib "2502-GMQLITE-MAIN") (part "RESCHP0097 100K 1% 0402 SMD"))
    )
    (comp (ref "R95")
      (value "10K")
      (footprint "RES-CHP0402-0.35H")
      (description "RES CHP 100K 1% 1/16W 0402 SMD")
      (libsource (lib "2502-GMQLITE-MAIN") (part "RESCHP0097 100K 1% 0402 SMD"))
    )
    (comp (ref "R96")
      (value "22R")
      (footprint "RES-CHP0402-0.35H")
      (description "RES CHP 100K 1% 1/16W 0402 SMD")
      (libsource (lib "2502-GMQLITE-MAIN") (part "RESCHP0097 100K 1% 0402 SMD"))
    )
    (comp (ref "R97")
      (value "22R")
      (footprint "RES-CHP0402-0.35H")
      (description "RES CHP 100K 1% 1/16W 0402 SMD")
      (libsource (lib "2502-GMQLITE-MAIN") (part "RESCHP0097 100K 1% 0402 SMD"))
    )
    (comp (ref "R98")
      (value "22R")
      (footprint "RES-CHP0402-0.35H")
      (description "RES CHP 100K 1% 1/16W 0402 SMD")
      (libsource (lib "2502-GMQLITE-MAIN") (part "RESCHP0097 100K 1% 0402 SMD"))
    )
    (comp (ref "U4")
      (value "STM32F427VIT6")
      (footprint "QFP50P1600X1600X160-100N")
      (fields (field (name "MF") "STMicroelectronics"))
      (libsource (lib "STM32F427VIT6") (part "STM32F427VIT6"))
    )
    (comp (ref "U5")
      (value "STM32F427VIT6")
      (footprint "QFP50P1600X1600X160-100N")
      (fields (field (name "MF") "STMicroelectronics"))
      (libsource (lib "STM32F427VIT6") (part "STM32F427VIT6"))
    )
    (comp (ref "U6")
      (value "STM32F427VIT6")
      (footprint "QFP50P1600X1600X160-100N")
      (fields (field (name "MF") "STMicroelectronics"))
      (libsource (lib "STM32F427VIT6") (part "STM32F427VIT6"))
    )
    (comp (ref "Y1")
      (value "C3E-8Mhz")
      (footprint "XTAL_C3E-8.000-8-1015-R")
      (fields (field (name "MP") "C3E-8.000-8-1015-R"))
      (libsource (lib "C3E-8.000-8-1015-R") (part "C3E-8.000-8-1015-R"))
    )
    (comp (ref "Y2")
      (value "ABS07-120-32.768KHZ-T")
      (footprint "XTAL_ABS07-120-32.768KHZ-T")
      (description "32.768 kHz Â±20ppm Crystal 6pF 55 kOhms 2-SMD, No Lead")
      (fields (field (name "MF") "Abracon") (field (name "DIGI-KEY_PART_NUMBER") "535-11937-2-ND"))
      (libsource (lib "ABS07-120-32.768KHZ-T") (part "ABS07-120-32.768KHZ-T"))
    )
    (comp (ref "Y3")
      (value "C3E-8Mhz")
      (footprint "XTAL_C3E-8.000-8-1015-R")
      (fields (field (name "MP") "C3E-8.000-8-1015-R"))
      (libsource (lib "C3E-8.000-8-1015-R") (part "C3E-8.000-8-1015-R"))
    )
    (comp (ref "Y4")
      (value "ABS07-120-32.768KHZ-T")
      (footprint "XTAL_ABS07-120-32.768KHZ-T")
      (description "32.768 kHz Â±20ppm Crystal 6pF 55 kOhms 2-SMD, No Lead")
      (fields (field (name "MF") "Abracon") (field (name "DIGI-KEY_PART_NUMBER") "535-11937-2-ND"))
      (libsource (lib "ABS07-120-32.768KHZ-T") (part "ABS07-120-32.768KHZ-T"))
    )
    (comp (ref "Y5")
      (value "C3E-8Mhz")
      (footprint "XTAL_C3E-8.000-8-1015-R")
      (fields (field (name "MP") "C3E-8.000-8-1015-R"))
      (libsource (lib "C3E-8.000-8-1015-R") (part "C3E-8.000-8-1015-R"))
    )
    (comp (ref "Y6")
      (value "ABS07-120-32.768KHZ-T")
      (footprint "XTAL_ABS07-120-32.768KHZ-T")
      (description "32.768 kHz Â±20ppm Crystal 6pF 55 kOhms 2-SMD, No Lead")
      (fields (field (name "MF") "Abracon") (field (name "DIGI-KEY_PART_NUMBER") "535-11937-2-ND"))
      (libsource (lib "ABS07-120-32.768KHZ-T") (part "ABS07-120-32.768KHZ-T"))
    )
  )
  (nets
    (net (code "14") (name "/CTS") (class "Default")
      (node (ref "R18") (pin "2") (pinfunction "2_2") (pintype "passive"))
    )
    (net (code "15") (name "/EXTINT") (class "Default")
      (node (ref "R14") (pin "2") (pinfunction "2_2") (pintype "passive"))
    )
    (net (code "16") (name "/IMU_CS") (class "Default")
      (node (ref "R23") (pin "2") (pinfunction "2_2") (pintype "passive"))
    )
    (net (code "17") (name "/IMU_INT") (class "Default")
      (node (ref "R24") (pin "2") (pinfunction "2_2") (pintype "passive"))
    )
    (net (code "18") (name "/IMU_SCLK") (class "Default")
      (node (ref "R22") (pin "2") (pinfunction "2_2") (pintype "passive"))
    )
    (net (code "19") (name "/IMU_SDIO") (class "Default")
      (node (ref "R20") (pin "2") (pinfunction "2_2") (pintype "passive"))
    )
    (net (code "20") (name "/IMU_SDO") (class "Default")
      (node (ref "R21") (pin "2") (pinfunction "2_2") (pintype "passive"))
    )
    (net (code "21") (name "/MAG_C1") (class "Default")
      (node (ref "R84") (pin "1") (pinfunction "1_1") (pintype "passive"))
    )
    (net (code "22") (name "/MAG_CS") (class "Default")
      (node (ref "R35") (pin "2") (pinfunction "2_2") (pintype "passive"))
    )
    (net (code "23") (name "/MAG_DRDY") (class "Default")
      (node (ref "R83") (pin "1") (pinfunction "1_1") (pintype "passive"))
    )
    (net (code "24") (name "/MAG_INT") (class "Default")
      (node (ref "R31") (pin "2") (pinfunction "2_2") (pintype "passive"))
    )
    (net (code "25") (name "/MAG_SCL") (class "Default")
      (node (ref "R34") (pin "2") (pinfunction "2_2") (pintype "passive"))
    )
    (net (code "26") (name "/MAG_SDA") (class "Default")
      (node (ref "R32") (pin "2") (pinfunction "2_2") (pintype "passive"))
    )
    (net (code "27") (name "/MAG_SDO") (class "Default")
      (node (ref "R33") (pin "2") (pinfunction "2_2") (pintype "passive"))
    )
    (net (code "28") (name "/NRST") (class "Default")
      (node (ref "C47") (pin "2") (pinfunction "2_2") (pintype "passive"))
      (node (ref "R47") (pin "1") (pinfunction "1_1") (pintype "passive"))
      (node (ref "U5") (pin "14") (pinfunction "~{NRST}_14") (pintype "input"))
    )
    (net (code "29") (name "/NRST1") (class "Default")
      (node (ref "C30") (pin "2") (pinfunction "2_2") (pintype "passive"))
      (node (ref "R9") (pin "1") (pinfunction "1_1") (pintype "passive"))
      (node (ref "U4") (pin "14") (pinfunction "~{NRST}_14") (pintype "input"))
    )
    (net (code "30") (name "/NRST2") (class "Default")
      (node (ref "C64") (pin "2") (pinfunction "2_2") (pintype "passive"))
      (node (ref "R62") (pin "1") (pinfunction "1_1") (pintype "passive"))
      (node (ref "U6") (pin "14") (pinfunction "~{NRST}_14") (pintype "input"))
    )
    (net (code "31") (name "/ON{slash}SLEEP") (class "Default")
      (node (ref "R19") (pin "2") (pinfunction "2_2") (pintype "passive"))
    )
    (net (code "32") (name "/PI_MISO") (class "Default")
      (node (ref "J1") (pin "2") (pinfunction "2_2") (pintype "passive"))
      (node (ref "R58") (pin "2") (pinfunction "2_2") (pintype "passive"))
    )
    (net (code "33") (name "/PI_MOSI") (class "Default")
      (node (ref "J1") (pin "3") (pinfunction "3_3") (pintype "passive"))
      (node (ref "R57") (pin "2") (pinfunction "2_2") (pintype "passive"))
    )
    (net (code "34") (name "/PI_NSS") (class "Default")
      (node (ref "J1") (pin "1") (pinfunction "1_1") (pintype "passive"))
      (node (ref "R59") (pin "2") (pinfunction "2_2") (pintype "passive"))
    )
    (net (code "35") (name "/PI_RX") (class "Default")
      (node (ref "J1") (pin "6") (pinfunction "6_6") (pintype "passive"))
      (node (ref "R55") (pin "2") (pinfunction "2_2") (pintype "passive"))
    )
    (net (code "36") (name "/PI_SCK") (class "Default")
      (node (ref "J1") (pin "4") (pinfunction "4_4") (pintype "passive"))
      (node (ref "R56") (pin "2") (pinfunction "2_2") (pintype "passive"))
    )
    (net (code "37") (name "/PI_TX") (class "Default")
      (node (ref "J1") (pin "5") (pinfunction "5_5") (pintype "passive"))
      (node (ref "R60") (pin "1") (pinfunction "1_1") (pintype "passive"))
    )
    (net (code "38") (name "/PYRO") (class "Default")
      (node (ref "R88") (pin "1") (pinfunction "1_1") (pintype "passive"))
    )
    (net (code "39") (name "/PYROC2") (class "Default")
      (node (ref "R93") (pin "1") (pinfunction "1_1") (pintype "passive"))
    )
    (net (code "40") (name "/RESET_GPS") (class "Default")
      (node (ref "R76") (pin "1") (pinfunction "1_1") (pintype "passive"))
    )
    (net (code "41") (name "/RESET_RF") (class "Default")
      (node (ref "R78") (pin "1") (pinfunction "1_1") (pintype "passive"))
    )
    (net (code "42") (name "/RST") (class "Default")
      (node (ref "R17") (pin "2") (pinfunction "2_2") (pintype "passive"))
    )
    (net (code "43") (name "/SCL") (class "Default")
      (node (ref "R64") (pin "2") (pinfunction "2_2") (pintype "passive"))
      (node (ref "R68") (pin "2") (pinfunction "2_2") (pintype "passive"))
      (node (ref "R95") (pin "1") (pinfunction "1_1") (pintype "passive"))
    )
    (net (code "44") (name "/SDA") (class "Default")
      (node (ref "R66") (pin "2") (pinfunction "2_2") (pintype "passive"))
      (node (ref "R69") (pin "2") (pinfunction "2_2") (pintype "passive"))
      (node (ref "R94") (pin "1") (pinfunction "1_1") (pintype "passive"))
    )
    (net (code "45") (name "/SD_CLK") (class "Default")
      (node (ref "R36") (pin "2") (pinfunction "2_2") (pintype "passive"))
    )
    (net (code "46") (name "/SD_CMD") (class "Default")
      (node (ref "R41") (pin "2") (pinfunction "2_2") (pintype "passive"))
    )
    (net (code "47") (name "/SD_DAT0") (class "Default")
      (node (ref "R40") (pin "2") (pinfunction "2_2") (pintype "passive"))
    )
    (net (code "48") (name "/SD_DAT1") (class "Default")
      (node (ref "R39") (pin "2") (pinfunction "2_2") (pintype "passive"))
    )
    (net (code "49") (name "/SD_DAT2") (class "Default")
      (node (ref "R38") (pin "2") (pinfunction "2_2") (pintype "passive"))
    )
    (net (code "50") (name "/SD_DAT3") (class "Default")
      (node (ref "R37") (pin "2") (pinfunction "2_2") (pintype "passive"))
    )
    (net (code "51") (name "/SD_DET") (class "Default")
      (node (ref "R45") (pin "2") (pinfunction "2_2") (pintype "passive"))
    )
    (net (code "52") (name "/SERVO1") (class "Default")
      (node (ref "R71") (pin "2") (pinfunction "2_2") (pintype "passive"))
    )
    (net (code "53") (name "/SERVO2") (class "Default")
      (node (ref "R72") (pin "2") (pinfunction "2_2") (pintype "passive"))
    )
    (net (code "54") (name "/SERVO3") (class "Default")
      (node (ref "R73") (pin "2") (pinfunction "2_2") (pintype "passive"))
    )
    (net (code "55") (name "/SERVO4") (class "Default")
      (node (ref "R70") (pin "1") (pinfunction "1_1") (pintype "passive"))
    )
    (net (code "56") (name "/SERVO5") (class "Default")
      (node (ref "R65") (pin "1") (pinfunction "1_1") (pintype "passive"))
    )
    (net (code "57") (name "/SERVO6") (class "Default")
      (node (ref "R67") (pin "1") (pinfunction "1_1") (pintype "passive"))
    )
    (net (code "58") (name "/SPI2_MISO") (class "Default")
      (node (ref "R43") (pin "2") (pinfunction "2_2") (pintype "passive"))
    )
    (net (code "59") (name "/SPI2_MOSI") (class "Default")
      (node (ref "R42") (pin "2") (pinfunction "2_2") (pintype "passive"))
    )
    (net (code "60") (name "/SPI2_NSS") (class "Default")
      (node (ref "R46") (pin "2") (pinfunction "2_2") (pintype "passive"))
    )
    (net (code "61") (name "/SPI2_SCK") (class "Default")
      (node (ref "R44") (pin "2") (pinfunction "2_2") (pintype "passive"))
    )
    (net (code "62") (name "/SWCLK") (class "Default")
      (node (ref "R29") (pin "2") (pinfunction "2_2") (pintype "passive"))
    )
    (net (code "63") (name "/SWCLK2") (class "Default")
      (node (ref "R49") (pin "2") (pinfunction "2_2") (pintype "passive"))
    )
    (net (code "64") (name "/SWCLK3") (class "Default")
      (node (ref "R86") (pin "2") (pinfunction "2_2") (pintype "passive"))
    )
    (net (code "65") (name "/SWDIO") (class "Default")
      (node (ref "R30") (pin "2") (pinfunction "2_2") (pintype "passive"))
    )
    (net (code "66") (name "/SWDIO2") (class "Default")
      (node (ref "R50") (pin "2") (pinfunction "2_2") (pintype "passive"))
    )
    (net (code "67") (name "/SWDIO3") (class "Default")
      (node (ref "R87") (pin "2") (pinfunction "2_2") (pintype "passive"))
    )
    (net (code "68") (name "/TIMEPUL") (class "Default")
      (node (ref "R13") (pin "2") (pinfunction "2_2") (pintype "passive"))
    )
    (net (code "69") (name "/UART7_Rx") (class "Default")
      (node (ref "R11") (pin "2") (pinfunction "2_2") (pintype "passive"))
    )
    (net (code "70") (name "/UART7_Rx2") (class "Default")
      (node (ref "R75") (pin "2") (pinfunction "2_2") (pintype "passive"))
      (node (ref "R98") (pin "2") (pinfunction "2_2") (pintype "passive"))
    )
    (net (code "71") (name "/UART7_Tx") (class "Default")
      (node (ref "R12") (pin "2") (pinfunction "2_2") (pintype "passive"))
    )
    (net (code "72") (name "/UART7_Tx2") (class "Default")
      (node (ref "R96") (pin "2") (pinfunction "2_2") (pintype "passive"))
      (node (ref "R97") (pin "2") (pinfunction "2_2") (pintype "passive"))
    )
    (net (code "73") (name "/USART1_RX") (class "Default")
      (node (ref "R25") (pin "2") (pinfunction "2_2") (pintype "passive"))
      (node (ref "R54") (pin "2") (pinfunction "2_2") (pintype "passive"))
    )
    (net (code "74") (name "/USART1_TX") (class "Default")
      (node (ref "R26") (pin "2") (pinfunction "2_2") (pintype "passive"))
      (node (ref "R53") (pin "2") (pinfunction "2_2") (pintype "passive"))
    )
    (net (code "75") (name "/USART3_RX") (class "Default")
      (node (ref "R16") (pin "2") (pinfunction "2_2") (pintype "passive"))
    )
    (net (code "76") (name "/USART3_TX") (class "Default")
      (node (ref "R15") (pin "2") (pinfunction "2_2") (pintype "passive"))
    )
    (net (code "77") (name "/USB2_N") (class "Default")
      (node (ref "R52") (pin "2") (pinfunction "2_2") (pintype "passive"))
    )
    (net (code "78") (name "/USB2_P") (class "Default")
      (node (ref "R51") (pin "2") (pinfunction "2_2") (pintype "passive"))
    )
    (net (code "79") (name "/USB_N") (class "Default")
      (node (ref "R28") (pin "2") (pinfunction "2_2") (pintype "passive"))
    )
    (net (code "80") (name "/USB_P") (class "Default")
      (node (ref "R27") (pin "2") (pinfunction "2_2") (pintype "passive"))
    )
    (net (code "93") (name "3.3VA") (class "Default")
      (node (ref "C18") (pin "2") (pinfunction "2_2") (pintype "passive"))
      (node (ref "C19") (pin "2") (pinfunction "2_2") (pintype "passive"))
      (node (ref "C20") (pin "2") (pinfunction "2_2") (pintype "passive"))
      (node (ref "C21") (pin "2") (pinfunction "2_2") (pintype "passive"))
      (node (ref "C22") (pin "2") (pinfunction "2_2") (pintype "passive"))
      (node (ref "C23") (pin "2") (pinfunction "2_2") (pintype "passive"))
      (node (ref "C24") (pin "2") (pinfunction "2_2") (pintype "passive"))
      (node (ref "C25") (pin "2") (pinfunction "2_2") (pintype "passive"))
      (node (ref "C26") (pin "2") (pinfunction "2_2") (pintype "passive"))
      (node (ref "C27") (pin "2") (pinfunction "2_2") (pintype "passive"))
      (node (ref "C28") (pin "2") (pinfunction "2_2") (pintype "passive"))
      (node (ref "C29") (pin "2") (pinfunction "2_2") (pintype "passive"))
      (node (ref "C35") (pin "2") (pinfunction "2_2") (pintype "passive"))
      (node (ref "C36") (pin "2") (pinfunction "2_2") (pintype "passive"))
      (node (ref "C37") (pin "2") (pinfunction "2_2") (pintype "passive"))
      (node (ref "C38") (pin "2") (pinfunction "2_2") (pintype "passive"))
      (node (ref "C39") (pin "2") (pinfunction "2_2") (pintype "passive"))
      (node (ref "C40") (pin "2") (pinfunction "2_2") (pintype "passive"))
      (node (ref "C41") (pin "2") (pinfunction "2_2") (pintype "passive"))
      (node (ref "C42") (pin "2") (pinfunction "2_2") (pintype "passive"))
      (node (ref "C43") (pin "2") (pinfunction "2_2") (pintype "passive"))
      (node (ref "C44") (pin "2") (pinfunction "2_2") (pintype "passive"))
      (node (ref "C45") (pin "2") (pinfunction "2_2") (pintype "passive"))
      (node (ref "C46") (pin "2") (pinfunction "2_2") (pintype "passive"))
      (node (ref "C52") (pin "2") (pinfunction "2_2") (pintype "passive"))
      (node (ref "C53") (pin "2") (pinfunction "2_2") (pintype "passive"))
      (node (ref "C54") (pin "2") (pinfunction "2_2") (pintype "passive"))
      (node (ref "C55") (pin "2") (pinfunction "2_2") (pintype "passive"))
      (node (ref "C56") (pin "2") (pinfunction "2_2") (pintype "passive"))
      (node (ref "C57") (pin "2") (pinfunction "2_2") (pintype "passive"))
      (node (ref "C58") (pin "2") (pinfunction "2_2") (pintype "passive"))
      (node (ref "C59") (pin "2") (pinfunction "2_2") (pintype "passive"))
      (node (ref "C60") (pin "2") (pinfunction "2_2") (pintype "passive"))
      (node (ref "C61") (pin "2") (pinfunction "2_2") (pintype "passive"))
      (node (ref "C62") (pin "2") (pinfunction "2_2") (pintype "passive"))
      (node (ref "C63") (pin "2") (pinfunction "2_2") (pintype "passive"))
      (node (ref "P1") (pin "1") (pinfunction "1_1") (pintype "passive"))
      (node (ref "P3") (pin "1") (pinfunction "1_1") (pintype "passive"))
      (node (ref "P5") (pin "1") (pinfunction "1_1") (pintype "passive"))
      (node (ref "R47") (pin "2") (pinfunction "2_2") (pintype "passive"))
      (node (ref "R62") (pin "2") (pinfunction "2_2") (pintype "passive"))
      (node (ref "R9") (pin "2") (pinfunction "2_2") (pintype "passive"))
      (node (ref "R94") (pin "2") (pinfunction "2_2") (pintype "passive"))
      (node (ref "R95") (pin "2") (pinfunction "2_2") (pintype "passive"))
      (node (ref "U4") (pin "100") (pinfunction "VDD_100") (pintype "power_in"))
      (node (ref "U4") (pin "11") (pinfunction "VDD_11") (pintype "power_in"))
      (node (ref "U4") (pin "19") (pinfunction "VDD_19") (pintype "power_in"))
      (node (ref "U4") (pin "21") (pinfunction "VREF+_21") (pintype "power_in"))
      (node (ref "U4") (pin "22") (pinfunction "VDDA_22") (pintype "power_in"))
      (node (ref "U4") (pin "28") (pinfunction "VDD_28") (pintype "power_in"))
      (node (ref "U4") (pin "49") (pinfunction "VCAP_1_49") (pintype "passive"))
      (node (ref "U4") (pin "50") (pinfunction "VDD_50") (pintype "power_in"))
      (node (ref "U4") (pin "6") (pinfunction "VBAT_6") (pintype "power_in"))
      (node (ref "U4") (pin "73") (pinfunction "VCAP_2_73") (pintype "passive"))
      (node (ref "U4") (pin "75") (pinfunction "VDD_75") (pintype "power_in"))
      (node (ref "U5") (pin "100") (pinfunction "VDD_100") (pintype "power_in"))
      (node (ref "U5") (pin "11") (pinfunction "VDD_11") (pintype "power_in"))
      (node (ref "U5") (pin "19") (pinfunction "VDD_19") (pintype "power_in"))
      (node (ref "U5") (pin "21") (pinfunction "VREF+_21") (pintype "power_in"))
      (node (ref "U5") (pin "22") (pinfunction "VDDA_22") (pintype "power_in"))
      (node (ref "U5") (pin "28") (pinfunction "VDD_28") (pintype "power_in"))
      (node (ref "U5") (pin "49") (pinfunction "VCAP_1_49") (pintype "passive"))
      (node (ref "U5") (pin "50") (pinfunction "VDD_50") (pintype "power_in"))
      (node (ref "U5") (pin "6") (pinfunction "VBAT_6") (pintype "power_in"))
      (node (ref "U5") (pin "73") (pinfunction "VCAP_2_73") (pintype "passive"))
      (node (ref "U5") (pin "75") (pinfunction "VDD_75") (pintype "power_in"))
      (node (ref "U6") (pin "100") (pinfunction "VDD_100") (pintype "power_in"))
      (node (ref "U6") (pin "11") (pinfunction "VDD_11") (pintype "power_in"))
      (node (ref "U6") (pin "19") (pinfunction "VDD_19") (pintype "power_in"))
      (node (ref "U6") (pin "21") (pinfunction "VREF+_21") (pintype "power_in"))
      (node (ref "U6") (pin "22") (pinfunction "VDDA_22") (pintype "power_in"))
      (node (ref "U6") (pin "28") (pinfunction "VDD_28") (pintype "power_in"))
      (node (ref "U6") (pin "49") (pinfunction "VCAP_1_49") (pintype "passive"))
      (node (ref "U6") (pin "50") (pinfunction "VDD_50") (pintype "power_in"))
      (node (ref "U6") (pin "6") (pinfunction "VBAT_6") (pintype "power_in"))
      (node (ref "U6") (pin "73") (pinfunction "VCAP_2_73") (pintype "passive"))
      (node (ref "U6") (pin "75") (pinfunction "VDD_75") (pintype "power_in"))
    )
    (net (code "94") (name "GND") (class "Default")
      (node (ref "C18") (pin "1") (pinfunction "1_1") (pintype "passive"))
      (node (ref "C19") (pin "1") (pinfunction "1_1") (pintype "passive"))
      (node (ref "C20") (pin "1") (pinfunction "1_1") (pintype "passive"))
      (node (ref "C21") (pin "1") (pinfunction "1_1") (pintype "passive"))
      (node (ref "C22") (pin "1") (pinfunction "1_1") (pintype "passive"))
      (node (ref "C23") (pin "1") (pinfunction "1_1") (pintype "passive"))
      (node (ref "C24") (pin "1") (pinfunction "1_1") (pintype "passive"))
      (node (ref "C25") (pin "1") (pinfunction "1_1") (pintype "passive"))
      (node (ref "C26") (pin "1") (pinfunction "1_1") (pintype "passive"))
      (node (ref "C27") (pin "1") (pinfunction "1_1") (pintype "passive"))
      (node (ref "C28") (pin "1") (pinfunction "1_1") (pintype "passive"))
      (node (ref "C29") (pin "1") (pinfunction "1_1") (pintype "passive"))
      (node (ref "C30") (pin "1") (pinfunction "1_1") (pintype "passive"))
      (node (ref "C31") (pin "1") (pinfunction "1_1") (pintype "passive"))
      (node (ref "C32") (pin "1") (pinfunction "1_1") (pintype "passive"))
      (node (ref "C35") (pin "1") (pinfunction "1_1") (pintype "passive"))
      (node (ref "C36") (pin "1") (pinfunction "1_1") (pintype "passive"))
      (node (ref "C37") (pin "1") (pinfunction "1_1") (pintype "passive"))
      (node (ref "C38") (pin "1") (pinfunction "1_1") (pintype "passive"))
      (node (ref "C39") (pin "1") (pinfunction "1_1") (pintype "passive"))
      (node (ref "C40") (pin "1") (pinfunction "1_1") (pintype "passive"))
      (node (ref "C41") (pin "1") (pinfunction "1_1") (pintype "passive"))
      (node (ref "C42") (pin "1") (pinfunction "1_1") (pintype "passive"))
      (node (ref "C43") (pin "1") (pinfunction "1_1") (pintype "passive"))
      (node (ref "C44") (pin "1") (pinfunction "1_1") (pintype "passive"))
      (node (ref "C46") (pin "1") (pinfunction "1_1") (pintype "passive"))
      (node (ref "C47") (pin "1") (pinfunction "1_1") (pintype "passive"))
      (node (ref "C50") (pin "1") (pinfunction "1_1") (pintype "passive"))
      (node (ref "C51") (pin "1") (pinfunction "1_1") (pintype "passive"))
      (node (ref "C52") (pin "1") (pinfunction "1_1") (pintype "passive"))
      (node (ref "C53") (pin "1") (pinfunction "1_1") (pintype "passive"))
      (node (ref "C54") (pin "1") (pinfunction "1_1") (pintype "passive"))
      (node (ref "C55") (pin "1") (pinfunction "1_1") (pintype "passive"))
      (node (ref "C56") (pin "1") (pinfunction "1_1") (pintype "passive"))
      (node (ref "C57") (pin "1") (pinfunction "1_1") (pintype "passive"))
      (node (ref "C58") (pin "1") (pinfunction "1_1") (pintype "passive"))
      (node (ref "C59") (pin "1") (pinfunction "1_1") (pintype "passive"))
      (node (ref "C60") (pin "1") (pinfunction "1_1") (pintype "passive"))
      (node (ref "C61") (pin "1") (pinfunction "1_1") (pintype "passive"))
      (node (ref "C62") (pin "1") (pinfunction "1_1") (pintype "passive"))
      (node (ref "C63") (pin "1") (pinfunction "1_1") (pintype "passive"))
      (node (ref "C64") (pin "1") (pinfunction "1_1") (pintype "passive"))
      (node (ref "C67") (pin "1") (pinfunction "1_1") (pintype "passive"))
      (node (ref "C68") (pin "1") (pinfunction "1_1") (pintype "passive"))
      (node (ref "J1") (pin "S1") (pinfunction "SHIELD1_S1") (pintype "passive"))
      (node (ref "J1") (pin "S2") (pinfunction "SHIELD2_S2") (pintype "passive"))
      (node (ref "P2") (pin "2") (pinfunction "2_2") (pintype "passive"))
      (node (ref "P4") (pin "2") (pinfunction "2_2") (pintype "passive"))
      (node (ref "P6") (pin "2") (pinfunction "2_2") (pintype "passive"))
      (node (ref "R10") (pin "1") (pinfunction "1_1") (pintype "passive"))
      (node (ref "R48") (pin "1") (pinfunction "1_1") (pintype "passive"))
      (node (ref "R61") (pin "2") (pinfunction "2_2") (pintype "passive"))
      (node (ref "R63") (pin "1") (pinfunction "1_1") (pintype "passive"))
      (node (ref "U4") (pin "10") (pinfunction "VSS_10") (pintype "power_in"))
      (node (ref "U4") (pin "20") (pinfunction "VSSA_20") (pintype "power_in"))
      (node (ref "U4") (pin "27") (pinfunction "VSS_27") (pintype "power_in"))
      (node (ref "U4") (pin "74") (pinfunction "VSS_74") (pintype "power_in"))
      (node (ref "U4") (pin "99") (pinfunction "VSS_99") (pintype "power_in"))
      (node (ref "U5") (pin "10") (pinfunction "VSS_10") (pintype "power_in"))
      (node (ref "U5") (pin "20") (pinfunction "VSSA_20") (pintype "power_in"))
      (node (ref "U5") (pin "27") (pinfunction "VSS_27") (pintype "power_in"))
      (node (ref "U5") (pin "74") (pinfunction "VSS_74") (pintype "power_in"))
      (node (ref "U5") (pin "99") (pinfunction "VSS_99") (pintype "power_in"))
      (node (ref "U6") (pin "10") (pinfunction "VSS_10") (pintype "power_in"))
      (node (ref "U6") (pin "20") (pinfunction "VSSA_20") (pintype "power_in"))
      (node (ref "U6") (pin "27") (pinfunction "VSS_27") (pintype "power_in"))
      (node (ref "U6") (pin "74") (pinfunction "VSS_74") (pintype "power_in"))
      (node (ref "U6") (pin "99") (pinfunction "VSS_99") (pintype "power_in"))
    )
    (net (code "95") (name "Net-(C33-Pad2)") (class "Default")
      (node (ref "C33") (pin "2") (pinfunction "2_2") (pintype "passive"))
      (node (ref "Y1") (pin "2") (pinfunction "GND_2") (pintype "power_in"))
    )
    (net (code "96") (name "Net-(C34-Pad2)") (class "Default")
      (node (ref "C34") (pin "2") (pinfunction "2_2") (pintype "passive"))
      (node (ref "Y1") (pin "4") (pinfunction "GND_4") (pintype "power_in"))
    )
    (net (code "97") (name "Net-(C48-Pad2)") (class "Default")
      (node (ref "C48") (pin "2") (pinfunction "2_2") (pintype "passive"))
      (node (ref "Y3") (pin "2") (pinfunction "GND_2") (pintype "power_in"))
    )
    (net (code "98") (name "Net-(C49-Pad2)") (class "Default")
      (node (ref "C49") (pin "2") (pinfunction "2_2") (pintype "passive"))
      (node (ref "Y3") (pin "4") (pinfunction "GND_4") (pintype "power_in"))
    )
    (net (code "99") (name "Net-(C65-Pad2)") (class "Default")
      (node (ref "C65") (pin "2") (pinfunction "2_2") (pintype "passive"))
      (node (ref "Y5") (pin "2") (pinfunction "GND_2") (pintype "power_in"))
    )
    (net (code "100") (name "Net-(C66-Pad2)") (class "Default")
      (node (ref "C66") (pin "2") (pinfunction "2_2") (pintype "passive"))
      (node (ref "Y5") (pin "4") (pinfunction "GND_4") (pintype "power_in"))
    )
    (net (code "101") (name "Net-(LD3-A)") (class "Default")
      (node (ref "LD3") (pin "1") (pinfunction "A_1") (pintype "passive"))
      (node (ref "U5") (pin "56") (pinfunction "PD9_56") (pintype "bidirectional"))
    )
    (net (code "102") (name "Net-(LD3-K)") (class "Default")
      (node (ref "LD3") (pin "2") (pinfunction "K_2") (pintype "passive"))
      (node (ref "R61") (pin "1") (pinfunction "1_1") (pintype "passive"))
    )
    (net (code "103") (name "Net-(U4A-PA1)") (class "Default")
      (node (ref "R76") (pin "2") (pinfunction "2_2") (pintype "passive"))
      (node (ref "U4") (pin "24") (pinfunction "PA1_24") (pintype "bidirectional"))
    )
    (net (code "104") (name "Net-(U4A-PA2)") (class "Default")
      (node (ref "R78") (pin "2") (pinfunction "2_2") (pintype "passive"))
      (node (ref "U4") (pin "25") (pinfunction "PA2_25") (pintype "bidirectional"))
    )
    (net (code "105") (name "Net-(U4A-PB6)") (class "Default")
      (node (ref "R83") (pin "2") (pinfunction "2_2") (pintype "passive"))
      (node (ref "U4") (pin "92") (pinfunction "PB6_92") (pintype "bidirectional"))
    )
    (net (code "106") (name "Net-(U4A-PB8)") (class "Default")
      (node (ref "R84") (pin "2") (pinfunction "2_2") (pintype "passive"))
      (node (ref "U4") (pin "95") (pinfunction "PB8_95") (pintype "bidirectional"))
    )
    (net (code "107") (name "Net-(U4C-BOOT0)") (class "Default")
      (node (ref "P1") (pin "2") (pinfunction "2_2") (pintype "passive"))
      (node (ref "P2") (pin "1") (pinfunction "1_1") (pintype "passive"))
      (node (ref "R10") (pin "2") (pinfunction "2_2") (pintype "passive"))
      (node (ref "U4") (pin "94") (pinfunction "BOOT0_94") (pintype "input"))
    )
    (net (code "108") (name "Net-(U4C-PC14-OSC32_IN)") (class "Default")
      (node (ref "C32") (pin "2") (pinfunction "2_2") (pintype "passive"))
      (node (ref "U4") (pin "8") (pinfunction "PC14-OSC32_IN_8") (pintype "bidirectional"))
      (node (ref "Y2") (pin "1") (pinfunction "1_1") (pintype "passive"))
    )
    (net (code "109") (name "Net-(U4C-PC15-OSC32_OUT)") (class "Default")
      (node (ref "C31") (pin "2") (pinfunction "2_2") (pintype "passive"))
      (node (ref "U4") (pin "9") (pinfunction "PC15-OSC32_OUT_9") (pintype "bidirectional"))
      (node (ref "Y2") (pin "2") (pinfunction "2_2") (pintype "passive"))
    )
    (net (code "110") (name "Net-(U4C-PH0-OSC_IN)") (class "Default")
      (node (ref "C33") (pin "1") (pinfunction "1_1") (pintype "passive"))
      (node (ref "U4") (pin "12") (pinfunction "PH0-OSC_IN_12") (pintype "bidirectional"))
      (node (ref "Y1") (pin "3") (pinfunction "2_3") (pintype "passive"))
    )
    (net (code "111") (name "Net-(U4C-PH1-OSC_OUT)") (class "Default")
      (node (ref "C34") (pin "1") (pinfunction "1_1") (pintype "passive"))
      (node (ref "U4") (pin "13") (pinfunction "PH1-OSC_OUT_13") (pintype "bidirectional"))
      (node (ref "Y1") (pin "1") (pinfunction "1_1") (pintype "passive"))
    )
    (net (code "112") (name "Net-(U4D-PA4)") (class "Default")
      (node (ref "R23") (pin "1") (pinfunction "1_1") (pintype "passive"))
      (node (ref "U4") (pin "29") (pinfunction "PA4_29") (pintype "bidirectional"))
    )
    (net (code "113") (name "Net-(U4D-PA5)") (class "Default")
      (node (ref "R22") (pin "1") (pinfunction "1_1") (pintype "passive"))
      (node (ref "U4") (pin "30") (pinfunction "PA5_30") (pintype "bidirectional"))
    )
    (net (code "114") (name "Net-(U4D-PA6)") (class "Default")
      (node (ref "R21") (pin "1") (pinfunction "1_1") (pintype "passive"))
      (node (ref "U4") (pin "31") (pinfunction "PA6_31") (pintype "bidirectional"))
    )
    (net (code "115") (name "Net-(U4D-PA7)") (class "Default")
      (node (ref "R20") (pin "1") (pinfunction "1_1") (pintype "passive"))
      (node (ref "U4") (pin "32") (pinfunction "PA7_32") (pintype "bidirectional"))
    )
    (net (code "116") (name "Net-(U4D-PA9)") (class "Default")
      (node (ref "R26") (pin "1") (pinfunction "1_1") (pintype "passive"))
      (node (ref "U4") (pin "68") (pinfunction "PA9_68") (pintype "bidirectional"))
    )
    (net (code "117") (name "Net-(U4D-PA10)") (class "Default")
      (node (ref "R25") (pin "1") (pinfunction "1_1") (pintype "passive"))
      (node (ref "U4") (pin "69") (pinfunction "PA10_69") (pintype "bidirectional"))
    )
    (net (code "118") (name "Net-(U4D-PA11)") (class "Default")
      (node (ref "R28") (pin "1") (pinfunction "1_1") (pintype "passive"))
      (node (ref "U4") (pin "70") (pinfunction "PA11_70") (pintype "bidirectional"))
    )
    (net (code "119") (name "Net-(U4D-PA12)") (class "Default")
      (node (ref "R27") (pin "1") (pinfunction "1_1") (pintype "passive"))
      (node (ref "U4") (pin "71") (pinfunction "PA12_71") (pintype "bidirectional"))
    )
    (net (code "120") (name "Net-(U4D-PA13(JTMS-SWDIO))") (class "Default")
      (node (ref "R30") (pin "1") (pinfunction "1_1") (pintype "passive"))
      (node (ref "U4") (pin "72") (pinfunction "PA13(JTMS-SWDIO)_72") (pintype "bidirectional"))
    )
    (net (code "121") (name "Net-(U4D-PA14(JTCK-SWCLK))") (class "Default")
      (node (ref "R29") (pin "1") (pinfunction "1_1") (pintype "passive"))
      (node (ref "U4") (pin "76") (pinfunction "PA14(JTCK-SWCLK)_76") (pintype "bidirectional"))
    )
    (net (code "122") (name "Net-(U4D-PB2-BOOT1)") (class "Default")
      (node (ref "R35") (pin "1") (pinfunction "1_1") (pintype "passive"))
      (node (ref "U4") (pin "37") (pinfunction "PB2-BOOT1_37") (pintype "bidirectional"))
    )
    (net (code "123") (name "Net-(U4D-PB3(JTDO{slash}TRACESWO))") (class "Default")
      (node (ref "R34") (pin "1") (pinfunction "1_1") (pintype "passive"))
      (node (ref "U4") (pin "89") (pinfunction "PB3(JTDO/TRACESWO)_89") (pintype "bidirectional"))
    )
    (net (code "124") (name "Net-(U4D-PB4(NJTRST))") (class "Default")
      (node (ref "R33") (pin "1") (pinfunction "1_1") (pintype "passive"))
      (node (ref "U4") (pin "90") (pinfunction "PB4(NJTRST)_90") (pintype "bidirectional"))
    )
    (net (code "125") (name "Net-(U4D-PB5)") (class "Default")
      (node (ref "R32") (pin "1") (pinfunction "1_1") (pintype "passive"))
      (node (ref "U4") (pin "91") (pinfunction "PB5_91") (pintype "bidirectional"))
    )
    (net (code "126") (name "Net-(U4D-PB7)") (class "Default")
      (node (ref "R31") (pin "1") (pinfunction "1_1") (pintype "passive"))
      (node (ref "U4") (pin "93") (pinfunction "PB7_93") (pintype "bidirectional"))
    )
    (net (code "127") (name "Net-(U4D-PB12)") (class "Default")
      (node (ref "R46") (pin "1") (pinfunction "1_1") (pintype "passive"))
      (node (ref "U4") (pin "51") (pinfunction "PB12_51") (pintype "bidirectional"))
    )
    (net (code "128") (name "Net-(U4D-PB13)") (class "Default")
      (node (ref "R44") (pin "1") (pinfunction "1_1") (pintype "passive"))
      (node (ref "U4") (pin "52") (pinfunction "PB13_52") (pintype "bidirectional"))
    )
    (net (code "129") (name "Net-(U4D-PB14)") (class "Default")
      (node (ref "R43") (pin "1") (pinfunction "1_1") (pintype "passive"))
      (node (ref "U4") (pin "53") (pinfunction "PB14_53") (pintype "bidirectional"))
    )
    (net (code "130") (name "Net-(U4D-PB15)") (class "Default")
      (node (ref "R42") (pin "1") (pinfunction "1_1") (pintype "passive"))
      (node (ref "U4") (pin "54") (pinfunction "PB15_54") (pintype "bidirectional"))
    )
    (net (code "131") (name "Net-(U4D-PC4)") (class "Default")
      (node (ref "R24") (pin "1") (pinfunction "1_1") (pintype "passive"))
      (node (ref "U4") (pin "33") (pinfunction "PC4_33") (pintype "bidirectional"))
    )
    (net (code "132") (name "Net-(U4D-PC8)") (class "Default")
      (node (ref "R40") (pin "1") (pinfunction "1_1") (pintype "passive"))
      (node (ref "U4") (pin "65") (pinfunction "PC8_65") (pintype "bidirectional"))
    )
    (net (code "133") (name "Net-(U4D-PC9)") (class "Default")
      (node (ref "R39") (pin "1") (pinfunction "1_1") (pintype "passive"))
      (node (ref "U4") (pin "66") (pinfunction "PC9_66") (pintype "bidirectional"))
    )
    (net (code "134") (name "Net-(U4D-PC10)") (class "Default")
      (node (ref "R38") (pin "1") (pinfunction "1_1") (pintype "passive"))
      (node (ref "U4") (pin "78") (pinfunction "PC10_78") (pintype "bidirectional"))
    )
    (net (code "135") (name "Net-(U4D-PC11)") (class "Default")
      (node (ref "R37") (pin "1") (pinfunction "1_1") (pintype "passive"))
      (node (ref "U4") (pin "79") (pinfunction "PC11_79") (pintype "bidirectional"))
    )
    (net (code "136") (name "Net-(U4D-PC12)") (class "Default")
      (node (ref "R36") (pin "1") (pinfunction "1_1") (pintype "passive"))
      (node (ref "U4") (pin "80") (pinfunction "PC12_80") (pintype "bidirectional"))
    )
    (net (code "137") (name "Net-(U4D-PC13)") (class "Default")
      (node (ref "R45") (pin "1") (pinfunction "1_1") (pintype "passive"))
      (node (ref "U4") (pin "7") (pinfunction "PC13_7") (pintype "bidirectional"))
    )
    (net (code "138") (name "Net-(U4D-PD2)") (class "Default")
      (node (ref "R41") (pin "1") (pinfunction "1_1") (pintype "passive"))
      (node (ref "U4") (pin "83") (pinfunction "PD2_83") (pintype "bidirectional"))
    )
    (net (code "139") (name "Net-(U4D-PD8)") (class "Default")
      (node (ref "R15") (pin "1") (pinfunction "1_1") (pintype "passive"))
      (node (ref "U4") (pin "55") (pinfunction "PD8_55") (pintype "bidirectional"))
    )
    (net (code "140") (name "Net-(U4D-PD9)") (class "Default")
      (node (ref "R16") (pin "1") (pinfunction "1_1") (pintype "passive"))
      (node (ref "U4") (pin "56") (pinfunction "PD9_56") (pintype "bidirectional"))
    )
    (net (code "141") (name "Net-(U4D-PD10)") (class "Default")
      (node (ref "R17") (pin "1") (pinfunction "1_1") (pintype "passive"))
      (node (ref "U4") (pin "57") (pinfunction "PD10_57") (pintype "bidirectional"))
    )
    (net (code "142") (name "Net-(U4D-PD11)") (class "Default")
      (node (ref "R18") (pin "1") (pinfunction "1_1") (pintype "passive"))
      (node (ref "U4") (pin "58") (pinfunction "PD11_58") (pintype "bidirectional"))
    )
    (net (code "143") (name "Net-(U4D-PD12)") (class "Default")
      (node (ref "R19") (pin "1") (pinfunction "1_1") (pintype "passive"))
      (node (ref "U4") (pin "59") (pinfunction "PD12_59") (pintype "bidirectional"))
    )
    (net (code "144") (name "Net-(U4D-PE7)") (class "Default")
      (node (ref "R11") (pin "1") (pinfunction "1_1") (pintype "passive"))
      (node (ref "U4") (pin "38") (pinfunction "PE7_38") (pintype "bidirectional"))
    )
    (net (code "145") (name "Net-(U4D-PE8)") (class "Default")
      (node (ref "R12") (pin "1") (pinfunction "1_1") (pintype "passive"))
      (node (ref "U4") (pin "39") (pinfunction "PE8_39") (pintype "bidirectional"))
    )
    (net (code "146") (name "Net-(U4D-PE9)") (class "Default")
      (node (ref "R13") (pin "1") (pinfunction "1_1") (pintype "passive"))
      (node (ref "U4") (pin "40") (pinfunction "PE9_40") (pintype "bidirectional"))
    )
    (net (code "147") (name "Net-(U4D-PE10)") (class "Default")
      (node (ref "R14") (pin "1") (pinfunction "1_1") (pintype "passive"))
      (node (ref "U4") (pin "41") (pinfunction "PE10_41") (pintype "bidirectional"))
    )
    (net (code "148") (name "Net-(U5A-PB6)") (class "Default")
      (node (ref "R60") (pin "2") (pinfunction "2_2") (pintype "passive"))
      (node (ref "U5") (pin "92") (pinfunction "PB6_92") (pintype "bidirectional"))
    )
    (net (code "149") (name "Net-(U5A-PB10)") (class "Default")
      (node (ref "R64") (pin "1") (pinfunction "1_1") (pintype "passive"))
      (node (ref "U5") (pin "47") (pinfunction "PB10_47") (pintype "bidirectional"))
    )
    (net (code "150") (name "Net-(U5A-PB11)") (class "Default")
      (node (ref "R66") (pin "1") (pinfunction "1_1") (pintype "passive"))
      (node (ref "U5") (pin "48") (pinfunction "PB11_48") (pintype "bidirectional"))
    )
    (net (code "151") (name "Net-(U5C-BOOT0)") (class "Default")
      (node (ref "P3") (pin "2") (pinfunction "2_2") (pintype "passive"))
      (node (ref "P4") (pin "1") (pinfunction "1_1") (pintype "passive"))
      (node (ref "R48") (pin "2") (pinfunction "2_2") (pintype "passive"))
      (node (ref "U5") (pin "94") (pinfunction "BOOT0_94") (pintype "input"))
    )
    (net (code "152") (name "Net-(U5C-PC14-OSC32_IN)") (class "Default")
      (node (ref "C51") (pin "2") (pinfunction "2_2") (pintype "passive"))
      (node (ref "U5") (pin "8") (pinfunction "PC14-OSC32_IN_8") (pintype "bidirectional"))
      (node (ref "Y4") (pin "1") (pinfunction "1_1") (pintype "passive"))
    )
    (net (code "153") (name "Net-(U5C-PC15-OSC32_OUT)") (class "Default")
      (node (ref "C50") (pin "2") (pinfunction "2_2") (pintype "passive"))
      (node (ref "U5") (pin "9") (pinfunction "PC15-OSC32_OUT_9") (pintype "bidirectional"))
      (node (ref "Y4") (pin "2") (pinfunction "2_2") (pintype "passive"))
    )
    (net (code "154") (name "Net-(U5C-PH0-OSC_IN)") (class "Default")
      (node (ref "C48") (pin "1") (pinfunction "1_1") (pintype "passive"))
      (node (ref "U5") (pin "12") (pinfunction "PH0-OSC_IN_12") (pintype "bidirectional"))
      (node (ref "Y3") (pin "3") (pinfunction "2_3") (pintype "passive"))
    )
    (net (code "155") (name "Net-(U5C-PH1-OSC_OUT)") (class "Default")
      (node (ref "C49") (pin "1") (pinfunction "1_1") (pintype "passive"))
      (node (ref "U5") (pin "13") (pinfunction "PH1-OSC_OUT_13") (pintype "bidirectional"))
      (node (ref "Y3") (pin "1") (pinfunction "1_1") (pintype "passive"))
    )
    (net (code "156") (name "Net-(U5D-PA9)") (class "Default")
      (node (ref "R54") (pin "1") (pinfunction "1_1") (pintype "passive"))
      (node (ref "U5") (pin "68") (pinfunction "PA9_68") (pintype "bidirectional"))
    )
    (net (code "157") (name "Net-(U5D-PA10)") (class "Default")
      (node (ref "R53") (pin "1") (pinfunction "1_1") (pintype "passive"))
      (node (ref "U5") (pin "69") (pinfunction "PA10_69") (pintype "bidirectional"))
    )
    (net (code "158") (name "Net-(U5D-PA11)") (class "Default")
      (node (ref "R52") (pin "1") (pinfunction "1_1") (pintype "passive"))
      (node (ref "U5") (pin "70") (pinfunction "PA11_70") (pintype "bidirectional"))
    )
    (net (code "159") (name "Net-(U5D-PA12)") (class "Default")
      (node (ref "R51") (pin "1") (pinfunction "1_1") (pintype "passive"))
      (node (ref "U5") (pin "71") (pinfunction "PA12_71") (pintype "bidirectional"))
    )
    (net (code "160") (name "Net-(U5D-PA13(JTMS-SWDIO))") (class "Default")
      (node (ref "R50") (pin "1") (pinfunction "1_1") (pintype "passive"))
      (node (ref "U5") (pin "72") (pinfunction "PA13(JTMS-SWDIO)_72") (pintype "bidirectional"))
    )
    (net (code "161") (name "Net-(U5D-PA14(JTCK-SWCLK))") (class "Default")
      (node (ref "R49") (pin "1") (pinfunction "1_1") (pintype "passive"))
      (node (ref "U5") (pin "76") (pinfunction "PA14(JTCK-SWCLK)_76") (pintype "bidirectional"))
    )
    (net (code "162") (name "Net-(U5D-PB3(JTDO{slash}TRACESWO))") (class "Default")
      (node (ref "R58") (pin "1") (pinfunction "1_1") (pintype "passive"))
      (node (ref "U5") (pin "89") (pinfunction "PB3(JTDO/TRACESWO)_89") (pintype "bidirectional"))
    )
    (net (code "163") (name "Net-(U5D-PB4(NJTRST))") (class "Default")
      (node (ref "R57") (pin "1") (pinfunction "1_1") (pintype "passive"))
      (node (ref "U5") (pin "90") (pinfunction "PB4(NJTRST)_90") (pintype "bidirectional"))
    )
    (net (code "164") (name "Net-(U5D-PB5)") (class "Default")
      (node (ref "R56") (pin "1") (pinfunction "1_1") (pintype "passive"))
      (node (ref "U5") (pin "91") (pinfunction "PB5_91") (pintype "bidirectional"))
    )
    (net (code "165") (name "Net-(U5D-PB7)") (class "Default")
      (node (ref "R55") (pin "1") (pinfunction "1_1") (pintype "passive"))
      (node (ref "U5") (pin "93") (pinfunction "PB7_93") (pintype "bidirectional"))
    )
    (net (code "166") (name "Net-(U5D-PB12)") (class "Default")
      (node (ref "R59") (pin "1") (pinfunction "1_1") (pintype "passive"))
      (node (ref "U5") (pin "51") (pinfunction "PB12_51") (pintype "bidirectional"))
    )
    (net (code "167") (name "Net-(U5D-PE7)") (class "Default")
      (node (ref "R75") (pin "1") (pinfunction "1_1") (pintype "passive"))
      (node (ref "U5") (pin "38") (pinfunction "PE7_38") (pintype "bidirectional"))
    )
    (net (code "168") (name "Net-(U5D-PE8)") (class "Default")
      (node (ref "R97") (pin "1") (pinfunction "1_1") (pintype "passive"))
      (node (ref "U5") (pin "39") (pinfunction "PE8_39") (pintype "bidirectional"))
    )
    (net (code "169") (name "Net-(U6A-PB6)") (class "Default")
      (node (ref "R71") (pin "1") (pinfunction "1_1") (pintype "passive"))
      (node (ref "U6") (pin "92") (pinfunction "PB6_92") (pintype "bidirectional"))
    )
    (net (code "170") (name "Net-(U6A-PB8)") (class "Default")
      (node (ref "R72") (pin "1") (pinfunction "1_1") (pintype "passive"))
      (node (ref "U6") (pin "95") (pinfunction "PB8_95") (pintype "bidirectional"))
    )
    (net (code "171") (name "Net-(U6A-PB9)") (class "Default")
      (node (ref "R73") (pin "1") (pinfunction "1_1") (pintype "passive"))
      (node (ref "U6") (pin "96") (pinfunction "PB9_96") (pintype "bidirectional"))
    )
    (net (code "172") (name "Net-(U6A-PB10)") (class "Default")
      (node (ref "R68") (pin "1") (pinfunction "1_1") (pintype "passive"))
      (node (ref "U6") (pin "47") (pinfunction "PB10_47") (pintype "bidirectional"))
    )
    (net (code "173") (name "Net-(U6A-PB11)") (class "Default")
      (node (ref "R69") (pin "1") (pinfunction "1_1") (pintype "passive"))
      (node (ref "U6") (pin "48") (pinfunction "PB11_48") (pintype "bidirectional"))
    )
    (net (code "174") (name "Net-(U6C-BOOT0)") (class "Default")
      (node (ref "P5") (pin "2") (pinfunction "2_2") (pintype "passive"))
      (node (ref "P6") (pin "1") (pinfunction "1_1") (pintype "passive"))
      (node (ref "R63") (pin "2") (pinfunction "2_2") (pintype "passive"))
      (node (ref "U6") (pin "94") (pinfunction "BOOT0_94") (pintype "input"))
    )
    (net (code "175") (name "Net-(U6C-PC14-OSC32_IN)") (class "Default")
      (node (ref "C68") (pin "2") (pinfunction "2_2") (pintype "passive"))
      (node (ref "U6") (pin "8") (pinfunction "PC14-OSC32_IN_8") (pintype "bidirectional"))
      (node (ref "Y6") (pin "1") (pinfunction "1_1") (pintype "passive"))
    )
    (net (code "176") (name "Net-(U6C-PC15-OSC32_OUT)") (class "Default")
      (node (ref "C67") (pin "2") (pinfunction "2_2") (pintype "passive"))
      (node (ref "U6") (pin "9") (pinfunction "PC15-OSC32_OUT_9") (pintype "bidirectional"))
      (node (ref "Y6") (pin "2") (pinfunction "2_2") (pintype "passive"))
    )
    (net (code "177") (name "Net-(U6C-PH0-OSC_IN)") (class "Default")
      (node (ref "C65") (pin "1") (pinfunction "1_1") (pintype "passive"))
      (node (ref "U6") (pin "12") (pinfunction "PH0-OSC_IN_12") (pintype "bidirectional"))
      (node (ref "Y5") (pin "3") (pinfunction "2_3") (pintype "passive"))
    )
    (net (code "178") (name "Net-(U6C-PH1-OSC_OUT)") (class "Default")
      (node (ref "C66") (pin "1") (pinfunction "1_1") (pintype "passive"))
      (node (ref "U6") (pin "13") (pinfunction "PH1-OSC_OUT_13") (pintype "bidirectional"))
      (node (ref "Y5") (pin "1") (pinfunction "1_1") (pintype "passive"))
    )
    (net (code "179") (name "Net-(U6D-PA6)") (class "Default")
      (node (ref "R67") (pin "2") (pinfunction "2_2") (pintype "passive"))
      (node (ref "U6") (pin "31") (pinfunction "PA6_31") (pintype "bidirectional"))
    )
    (net (code "180") (name "Net-(U6D-PA7)") (class "Default")
      (node (ref "R65") (pin "2") (pinfunction "2_2") (pintype "passive"))
      (node (ref "U6") (pin "32") (pinfunction "PA7_32") (pintype "bidirectional"))
    )
    (net (code "181") (name "Net-(U6D-PA13(JTMS-SWDIO))") (class "Default")
      (node (ref "R87") (pin "1") (pinfunction "1_1") (pintype "passive"))
      (node (ref "U6") (pin "72") (pinfunction "PA13(JTMS-SWDIO)_72") (pintype "bidirectional"))
    )
    (net (code "182") (name "Net-(U6D-PA14(JTCK-SWCLK))") (class "Default")
      (node (ref "R86") (pin "1") (pinfunction "1_1") (pintype "passive"))
      (node (ref "U6") (pin "76") (pinfunction "PA14(JTCK-SWCLK)_76") (pintype "bidirectional"))
    )
    (net (code "183") (name "Net-(U6D-PB7)") (class "Default")
      (node (ref "R70") (pin "2") (pinfunction "2_2") (pintype "passive"))
      (node (ref "U6") (pin "93") (pinfunction "PB7_93") (pintype "bidirectional"))
    )
    (net (code "184") (name "Net-(U6D-PC8)") (class "Default")
      (node (ref "R88") (pin "2") (pinfunction "2_2") (pintype "passive"))
      (node (ref "U6") (pin "65") (pinfunction "PC8_65") (pintype "bidirectional"))
    )
    (net (code "185") (name "Net-(U6D-PD2)") (class "Default")
      (node (ref "R93") (pin "2") (pinfunction "2_2") (pintype "passive"))
      (node (ref "U6") (pin "83") (pinfunction "PD2_83") (pintype "bidirectional"))
    )
    (net (code "186") (name "Net-(U6D-PE7)") (class "Default")
      (node (ref "R96") (pin "1") (pinfunction "1_1") (pintype "passive"))
      (node (ref "U6") (pin "38") (pinfunction "PE7_38") (pintype "bidirectional"))
    )
    (net (code "187") (name "Net-(U6D-PE8)") (class "Default")
      (node (ref "R98") (pin "1") (pinfunction "1_1") (pintype "passive"))
      (node (ref "U6") (pin "39") (pinfunction "PE8_39") (pintype "bidirectional"))
    )
    (net (code "188") (name "unconnected-(C45-Pad1)") (class "Default")
      (node (ref "C45") (pin "1") (pinfunction "1_1") (pintype "passive"))
    )
    (net (code "189") (name "unconnected-(MH1-GND-Pad1)") (class "Default")
      (node (ref "MH1") (pin "1") (pinfunction "GND_1") (pintype "passive+no_connect"))
    )
    (net (code "190") (name "unconnected-(MH2-GND-Pad1)") (class "Default")
      (node (ref "MH2") (pin "1") (pinfunction "GND_1") (pintype "passive+no_connect"))
    )
    (net (code "191") (name "unconnected-(MH3-GND-Pad1)") (class "Default")
      (node (ref "MH3") (pin "1") (pinfunction "GND_1") (pintype "passive+no_connect"))
    )
    (net (code "192") (name "unconnected-(MH4-GND-Pad1)") (class "Default")
      (node (ref "MH4") (pin "1") (pinfunction "GND_1") (pintype "passive+no_connect"))
    )
    (net (code "193") (name "unconnected-(U4A-PA0-WKUP-Pad23)") (class "Default")
      (node (ref "U4") (pin "23") (pinfunction "PA0-WKUP_23") (pintype "bidirectional"))
    )
    (net (code "194") (name "unconnected-(U4A-PA3-Pad26)") (class "Default")
      (node (ref "U4") (pin "26") (pinfunction "PA3_26") (pintype "bidirectional"))
    )
    (net (code "195") (name "unconnected-(U4A-PA8-Pad67)") (class "Default")
      (node (ref "U4") (pin "67") (pinfunction "PA8_67") (pintype "bidirectional"))
    )
    (net (code "196") (name "unconnected-(U4A-PA15(JTDI)-Pad77)") (class "Default")
      (node (ref "U4") (pin "77") (pinfunction "PA15(JTDI)_77") (pintype "bidirectional"))
    )
    (net (code "197") (name "unconnected-(U4A-PB0-Pad35)") (class "Default")
      (node (ref "U4") (pin "35") (pinfunction "PB0_35") (pintype "bidirectional"))
    )
    (net (code "198") (name "unconnected-(U4A-PB1-Pad36)") (class "Default")
      (node (ref "U4") (pin "36") (pinfunction "PB1_36") (pintype "bidirectional"))
    )
    (net (code "199") (name "unconnected-(U4A-PB9-Pad96)") (class "Default")
      (node (ref "U4") (pin "96") (pinfunction "PB9_96") (pintype "bidirectional"))
    )
    (net (code "200") (name "unconnected-(U4A-PB10-Pad47)") (class "Default")
      (node (ref "U4") (pin "47") (pinfunction "PB10_47") (pintype "bidirectional"))
    )
    (net (code "201") (name "unconnected-(U4A-PB11-Pad48)") (class "Default")
      (node (ref "U4") (pin "48") (pinfunction "PB11_48") (pintype "bidirectional"))
    )
    (net (code "202") (name "unconnected-(U4A-PC0-Pad15)") (class "Default")
      (node (ref "U4") (pin "15") (pinfunction "PC0_15") (pintype "bidirectional"))
    )
    (net (code "203") (name "unconnected-(U4A-PC1-Pad16)") (class "Default")
      (node (ref "U4") (pin "16") (pinfunction "PC1_16") (pintype "bidirectional"))
    )
    (net (code "204") (name "unconnected-(U4A-PC2-Pad17)") (class "Default")
      (node (ref "U4") (pin "17") (pinfunction "PC2_17") (pintype "bidirectional"))
    )
    (net (code "205") (name "unconnected-(U4A-PC3-Pad18)") (class "Default")
      (node (ref "U4") (pin "18") (pinfunction "PC3_18") (pintype "bidirectional"))
    )
    (net (code "206") (name "unconnected-(U4A-PC5-Pad34)") (class "Default")
      (node (ref "U4") (pin "34") (pinfunction "PC5_34") (pintype "bidirectional"))
    )
    (net (code "207") (name "unconnected-(U4A-PC6-Pad63)") (class "Default")
      (node (ref "U4") (pin "63") (pinfunction "PC6_63") (pintype "bidirectional"))
    )
    (net (code "208") (name "unconnected-(U4A-PC7-Pad64)") (class "Default")
      (node (ref "U4") (pin "64") (pinfunction "PC7_64") (pintype "bidirectional"))
    )
    (net (code "209") (name "unconnected-(U4A-PD0-Pad81)") (class "Default")
      (node (ref "U4") (pin "81") (pinfunction "PD0_81") (pintype "bidirectional"))
    )
    (net (code "210") (name "unconnected-(U4A-PD1-Pad82)") (class "Default")
      (node (ref "U4") (pin "82") (pinfunction "PD1_82") (pintype "bidirectional"))
    )
    (net (code "211") (name "unconnected-(U4A-PD3-Pad84)") (class "Default")
      (node (ref "U4") (pin "84") (pinfunction "PD3_84") (pintype "bidirectional"))
    )
    (net (code "212") (name "unconnected-(U4A-PD4-Pad85)") (class "Default")
      (node (ref "U4") (pin "85") (pinfunction "PD4_85") (pintype "bidirectional"))
    )
    (net (code "213") (name "unconnected-(U4A-PD5-Pad86)") (class "Default")
      (node (ref "U4") (pin "86") (pinfunction "PD5_86") (pintype "bidirectional"))
    )
    (net (code "214") (name "unconnected-(U4A-PD6-Pad87)") (class "Default")
      (node (ref "U4") (pin "87") (pinfunction "PD6_87") (pintype "bidirectional"))
    )
    (net (code "215") (name "unconnected-(U4A-PD7-Pad88)") (class "Default")
      (node (ref "U4") (pin "88") (pinfunction "PD7_88") (pintype "bidirectional"))
    )
    (net (code "216") (name "unconnected-(U4A-PD13-Pad60)") (class "Default")
      (node (ref "U4") (pin "60") (pinfunction "PD13_60") (pintype "bidirectional"))
    )
    (net (code "217") (name "unconnected-(U4A-PD14-Pad61)") (class "Default")
      (node (ref "U4") (pin "61") (pinfunction "PD14_61") (pintype "bidirectional"))
    )
    (net (code "218") (name "unconnected-(U4A-PD15-Pad62)") (class "Default")
      (node (ref "U4") (pin "62") (pinfunction "PD15_62") (pintype "bidirectional"))
    )
    (net (code "219") (name "unconnected-(U4A-PE0-Pad97)") (class "Default")
      (node (ref "U4") (pin "97") (pinfunction "PE0_97") (pintype "bidirectional"))
    )
    (net (code "220") (name "unconnected-(U4A-PE1-Pad98)") (class "Default")
      (node (ref "U4") (pin "98") (pinfunction "PE1_98") (pintype "bidirectional"))
    )
    (net (code "221") (name "unconnected-(U4A-PE2-Pad1)") (class "Default")
      (node (ref "U4") (pin "1") (pinfunction "PE2_1") (pintype "bidirectional"))
    )
    (net (code "222") (name "unconnected-(U4A-PE3-Pad2)") (class "Default")
      (node (ref "U4") (pin "2") (pinfunction "PE3_2") (pintype "bidirectional"))
    )
    (net (code "223") (name "unconnected-(U4A-PE4-Pad3)") (class "Default")
      (node (ref "U4") (pin "3") (pinfunction "PE4_3") (pintype "bidirectional"))
    )
    (net (code "224") (name "unconnected-(U4A-PE5-Pad4)") (class "Default")
      (node (ref "U4") (pin "4") (pinfunction "PE5_4") (pintype "bidirectional"))
    )
    (net (code "225") (name "unconnected-(U4A-PE6-Pad5)") (class "Default")
      (node (ref "U4") (pin "5") (pinfunction "PE6_5") (pintype "bidirectional"))
    )
    (net (code "226") (name "unconnected-(U4A-PE11-Pad42)") (class "Default")
      (node (ref "U4") (pin "42") (pinfunction "PE11_42") (pintype "bidirectional"))
    )
    (net (code "227") (name "unconnected-(U4A-PE12-Pad43)") (class "Default")
      (node (ref "U4") (pin "43") (pinfunction "PE12_43") (pintype "bidirectional"))
    )
    (net (code "228") (name "unconnected-(U4A-PE13-Pad44)") (class "Default")
      (node (ref "U4") (pin "44") (pinfunction "PE13_44") (pintype "bidirectional"))
    )
    (net (code "229") (name "unconnected-(U4A-PE14-Pad45)") (class "Default")
      (node (ref "U4") (pin "45") (pinfunction "PE14_45") (pintype "bidirectional"))
    )
    (net (code "230") (name "unconnected-(U4A-PE15-Pad46)") (class "Default")
      (node (ref "U4") (pin "46") (pinfunction "PE15_46") (pintype "bidirectional"))
    )
    (net (code "231") (name "unconnected-(U5A-PA0-WKUP-Pad23)") (class "Default")
      (node (ref "U5") (pin "23") (pinfunction "PA0-WKUP_23") (pintype "bidirectional"))
    )
    (net (code "232") (name "unconnected-(U5A-PA1-Pad24)") (class "Default")
      (node (ref "U5") (pin "24") (pinfunction "PA1_24") (pintype "bidirectional"))
    )
    (net (code "233") (name "unconnected-(U5A-PA2-Pad25)") (class "Default")
      (node (ref "U5") (pin "25") (pinfunction "PA2_25") (pintype "bidirectional"))
    )
    (net (code "234") (name "unconnected-(U5A-PA3-Pad26)") (class "Default")
      (node (ref "U5") (pin "26") (pinfunction "PA3_26") (pintype "bidirectional"))
    )
    (net (code "235") (name "unconnected-(U5A-PA8-Pad67)") (class "Default")
      (node (ref "U5") (pin "67") (pinfunction "PA8_67") (pintype "bidirectional"))
    )
    (net (code "236") (name "unconnected-(U5A-PA15(JTDI)-Pad77)") (class "Default")
      (node (ref "U5") (pin "77") (pinfunction "PA15(JTDI)_77") (pintype "bidirectional"))
    )
    (net (code "237") (name "unconnected-(U5A-PB0-Pad35)") (class "Default")
      (node (ref "U5") (pin "35") (pinfunction "PB0_35") (pintype "bidirectional"))
    )
    (net (code "238") (name "unconnected-(U5A-PB1-Pad36)") (class "Default")
      (node (ref "U5") (pin "36") (pinfunction "PB1_36") (pintype "bidirectional"))
    )
    (net (code "239") (name "unconnected-(U5A-PB8-Pad95)") (class "Default")
      (node (ref "U5") (pin "95") (pinfunction "PB8_95") (pintype "bidirectional"))
    )
    (net (code "240") (name "unconnected-(U5A-PB9-Pad96)") (class "Default")
      (node (ref "U5") (pin "96") (pinfunction "PB9_96") (pintype "bidirectional"))
    )
    (net (code "241") (name "unconnected-(U5A-PC0-Pad15)") (class "Default")
      (node (ref "U5") (pin "15") (pinfunction "PC0_15") (pintype "bidirectional"))
    )
    (net (code "242") (name "unconnected-(U5A-PC1-Pad16)") (class "Default")
      (node (ref "U5") (pin "16") (pinfunction "PC1_16") (pintype "bidirectional"))
    )
    (net (code "243") (name "unconnected-(U5A-PC2-Pad17)") (class "Default")
      (node (ref "U5") (pin "17") (pinfunction "PC2_17") (pintype "bidirectional"))
    )
    (net (code "244") (name "unconnected-(U5A-PC3-Pad18)") (class "Default")
      (node (ref "U5") (pin "18") (pinfunction "PC3_18") (pintype "bidirectional"))
    )
    (net (code "245") (name "unconnected-(U5A-PC5-Pad34)") (class "Default")
      (node (ref "U5") (pin "34") (pinfunction "PC5_34") (pintype "bidirectional"))
    )
    (net (code "246") (name "unconnected-(U5A-PC6-Pad63)") (class "Default")
      (node (ref "U5") (pin "63") (pinfunction "PC6_63") (pintype "bidirectional"))
    )
    (net (code "247") (name "unconnected-(U5A-PC7-Pad64)") (class "Default")
      (node (ref "U5") (pin "64") (pinfunction "PC7_64") (pintype "bidirectional"))
    )
    (net (code "248") (name "unconnected-(U5A-PD0-Pad81)") (class "Default")
      (node (ref "U5") (pin "81") (pinfunction "PD0_81") (pintype "bidirectional"))
    )
    (net (code "249") (name "unconnected-(U5A-PD1-Pad82)") (class "Default")
      (node (ref "U5") (pin "82") (pinfunction "PD1_82") (pintype "bidirectional"))
    )
    (net (code "250") (name "unconnected-(U5A-PD3-Pad84)") (class "Default")
      (node (ref "U5") (pin "84") (pinfunction "PD3_84") (pintype "bidirectional"))
    )
    (net (code "251") (name "unconnected-(U5A-PD4-Pad85)") (class "Default")
      (node (ref "U5") (pin "85") (pinfunction "PD4_85") (pintype "bidirectional"))
    )
    (net (code "252") (name "unconnected-(U5A-PD5-Pad86)") (class "Default")
      (node (ref "U5") (pin "86") (pinfunction "PD5_86") (pintype "bidirectional"))
    )
    (net (code "253") (name "unconnected-(U5A-PD6-Pad87)") (class "Default")
      (node (ref "U5") (pin "87") (pinfunction "PD6_87") (pintype "bidirectional"))
    )
    (net (code "254") (name "unconnected-(U5A-PD7-Pad88)") (class "Default")
      (node (ref "U5") (pin "88") (pinfunction "PD7_88") (pintype "bidirectional"))
    )
    (net (code "255") (name "unconnected-(U5A-PD13-Pad60)") (class "Default")
      (node (ref "U5") (pin "60") (pinfunction "PD13_60") (pintype "bidirectional"))
    )
    (net (code "256") (name "unconnected-(U5A-PD14-Pad61)") (class "Default")
      (node (ref "U5") (pin "61") (pinfunction "PD14_61") (pintype "bidirectional"))
    )
    (net (code "257") (name "unconnected-(U5A-PD15-Pad62)") (class "Default")
      (node (ref "U5") (pin "62") (pinfunction "PD15_62") (pintype "bidirectional"))
    )
    (net (code "258") (name "unconnected-(U5A-PE0-Pad97)") (class "Default")
      (node (ref "U5") (pin "97") (pinfunction "PE0_97") (pintype "bidirectional"))
    )
    (net (code "259") (name "unconnected-(U5A-PE1-Pad98)") (class "Default")
      (node (ref "U5") (pin "98") (pinfunction "PE1_98") (pintype "bidirectional"))
    )
    (net (code "260") (name "unconnected-(U5A-PE2-Pad1)") (class "Default")
      (node (ref "U5") (pin "1") (pinfunction "PE2_1") (pintype "bidirectional"))
    )
    (net (code "261") (name "unconnected-(U5A-PE3-Pad2)") (class "Default")
      (node (ref "U5") (pin "2") (pinfunction "PE3_2") (pintype "bidirectional"))
    )
    (net (code "262") (name "unconnected-(U5A-PE4-Pad3)") (class "Default")
      (node (ref "U5") (pin "3") (pinfunction "PE4_3") (pintype "bidirectional"))
    )
    (net (code "263") (name "unconnected-(U5A-PE5-Pad4)") (class "Default")
      (node (ref "U5") (pin "4") (pinfunction "PE5_4") (pintype "bidirectional"))
    )
    (net (code "264") (name "unconnected-(U5A-PE6-Pad5)") (class "Default")
      (node (ref "U5") (pin "5") (pinfunction "PE6_5") (pintype "bidirectional"))
    )
    (net (code "265") (name "unconnected-(U5A-PE11-Pad42)") (class "Default")
      (node (ref "U5") (pin "42") (pinfunction "PE11_42") (pintype "bidirectional"))
    )
    (net (code "266") (name "unconnected-(U5A-PE12-Pad43)") (class "Default")
      (node (ref "U5") (pin "43") (pinfunction "PE12_43") (pintype "bidirectional"))
    )
    (net (code "267") (name "unconnected-(U5A-PE13-Pad44)") (class "Default")
      (node (ref "U5") (pin "44") (pinfunction "PE13_44") (pintype "bidirectional"))
    )
    (net (code "268") (name "unconnected-(U5A-PE14-Pad45)") (class "Default")
      (node (ref "U5") (pin "45") (pinfunction "PE14_45") (pintype "bidirectional"))
    )
    (net (code "269") (name "unconnected-(U5A-PE15-Pad46)") (class "Default")
      (node (ref "U5") (pin "46") (pinfunction "PE15_46") (pintype "bidirectional"))
    )
    (net (code "270") (name "unconnected-(U5D-PA4-Pad29)") (class "Default")
      (node (ref "U5") (pin "29") (pinfunction "PA4_29") (pintype "bidirectional"))
    )
    (net (code "271") (name "unconnected-(U5D-PA5-Pad30)") (class "Default")
      (node (ref "U5") (pin "30") (pinfunction "PA5_30") (pintype "bidirectional"))
    )
    (net (code "272") (name "unconnected-(U5D-PA6-Pad31)") (class "Default")
      (node (ref "U5") (pin "31") (pinfunction "PA6_31") (pintype "bidirectional"))
    )
    (net (code "273") (name "unconnected-(U5D-PA7-Pad32)") (class "Default")
      (node (ref "U5") (pin "32") (pinfunction "PA7_32") (pintype "bidirectional"))
    )
    (net (code "274") (name "unconnected-(U5D-PB2-BOOT1-Pad37)") (class "Default")
      (node (ref "U5") (pin "37") (pinfunction "PB2-BOOT1_37") (pintype "bidirectional"))
    )
    (net (code "275") (name "unconnected-(U5D-PB13-Pad52)") (class "Default")
      (node (ref "U5") (pin "52") (pinfunction "PB13_52") (pintype "bidirectional"))
    )
    (net (code "276") (name "unconnected-(U5D-PB14-Pad53)") (class "Default")
      (node (ref "U5") (pin "53") (pinfunction "PB14_53") (pintype "bidirectional"))
    )
    (net (code "277") (name "unconnected-(U5D-PB15-Pad54)") (class "Default")
      (node (ref "U5") (pin "54") (pinfunction "PB15_54") (pintype "bidirectional"))
    )
    (net (code "278") (name "unconnected-(U5D-PC4-Pad33)") (class "Default")
      (node (ref "U5") (pin "33") (pinfunction "PC4_33") (pintype "bidirectional"))
    )
    (net (code "279") (name "unconnected-(U5D-PC8-Pad65)") (class "Default")
      (node (ref "U5") (pin "65") (pinfunction "PC8_65") (pintype "bidirectional"))
    )
    (net (code "280") (name "unconnected-(U5D-PC9-Pad66)") (class "Default")
      (node (ref "U5") (pin "66") (pinfunction "PC9_66") (pintype "bidirectional"))
    )
    (net (code "281") (name "unconnected-(U5D-PC10-Pad78)") (class "Default")
      (node (ref "U5") (pin "78") (pinfunction "PC10_78") (pintype "bidirectional"))
    )
    (net (code "282") (name "unconnected-(U5D-PC11-Pad79)") (class "Default")
      (node (ref "U5") (pin "79") (pinfunction "PC11_79") (pintype "bidirectional"))
    )
    (net (code "283") (name "unconnected-(U5D-PC12-Pad80)") (class "Default")
      (node (ref "U5") (pin "80") (pinfunction "PC12_80") (pintype "bidirectional"))
    )
    (net (code "284") (name "unconnected-(U5D-PC13-Pad7)") (class "Default")
      (node (ref "U5") (pin "7") (pinfunction "PC13_7") (pintype "bidirectional"))
    )
    (net (code "285") (name "unconnected-(U5D-PD2-Pad83)") (class "Default")
      (node (ref "U5") (pin "83") (pinfunction "PD2_83") (pintype "bidirectional"))
    )
    (net (code "286") (name "unconnected-(U5D-PD8-Pad55)") (class "Default")
      (node (ref "U5") (pin "55") (pinfunction "PD8_55") (pintype "bidirectional+no_connect"))
    )
    (net (code "287") (name "unconnected-(U5D-PD10-Pad57)") (class "Default")
      (node (ref "U5") (pin "57") (pinfunction "PD10_57") (pintype "bidirectional+no_connect"))
    )
    (net (code "288") (name "unconnected-(U5D-PD11-Pad58)") (class "Default")
      (node (ref "U5") (pin "58") (pinfunction "PD11_58") (pintype "bidirectional+no_connect"))
    )
    (net (code "289") (name "unconnected-(U5D-PD12-Pad59)") (class "Default")
      (node (ref "U5") (pin "59") (pinfunction "PD12_59") (pintype "bidirectional+no_connect"))
    )
    (net (code "290") (name "unconnected-(U5D-PE9-Pad40)") (class "Default")
      (node (ref "U5") (pin "40") (pinfunction "PE9_40") (pintype "bidirectional+no_connect"))
    )
    (net (code "291") (name "unconnected-(U5D-PE10-Pad41)") (class "Default")
      (node (ref "U5") (pin "41") (pinfunction "PE10_41") (pintype "bidirectional+no_connect"))
    )
    (net (code "292") (name "unconnected-(U6A-PA0-WKUP-Pad23)") (class "Default")
      (node (ref "U6") (pin "23") (pinfunction "PA0-WKUP_23") (pintype "bidirectional"))
    )
    (net (code "293") (name "unconnected-(U6A-PA1-Pad24)") (class "Default")
      (node (ref "U6") (pin "24") (pinfunction "PA1_24") (pintype "bidirectional"))
    )
    (net (code "294") (name "unconnected-(U6A-PA2-Pad25)") (class "Default")
      (node (ref "U6") (pin "25") (pinfunction "PA2_25") (pintype "bidirectional"))
    )
    (net (code "295") (name "unconnected-(U6A-PA3-Pad26)") (class "Default")
      (node (ref "U6") (pin "26") (pinfunction "PA3_26") (pintype "bidirectional"))
    )
    (net (code "296") (name "unconnected-(U6A-PA8-Pad67)") (class "Default")
      (node (ref "U6") (pin "67") (pinfunction "PA8_67") (pintype "bidirectional"))
    )
    (net (code "297") (name "unconnected-(U6A-PA15(JTDI)-Pad77)") (class "Default")
      (node (ref "U6") (pin "77") (pinfunction "PA15(JTDI)_77") (pintype "bidirectional"))
    )
    (net (code "298") (name "unconnected-(U6A-PB0-Pad35)") (class "Default")
      (node (ref "U6") (pin "35") (pinfunction "PB0_35") (pintype "bidirectional"))
    )
    (net (code "299") (name "unconnected-(U6A-PB1-Pad36)") (class "Default")
      (node (ref "U6") (pin "36") (pinfunction "PB1_36") (pintype "bidirectional"))
    )
    (net (code "300") (name "unconnected-(U6A-PC0-Pad15)") (class "Default")
      (node (ref "U6") (pin "15") (pinfunction "PC0_15") (pintype "bidirectional"))
    )
    (net (code "301") (name "unconnected-(U6A-PC1-Pad16)") (class "Default")
      (node (ref "U6") (pin "16") (pinfunction "PC1_16") (pintype "bidirectional"))
    )
    (net (code "302") (name "unconnected-(U6A-PC2-Pad17)") (class "Default")
      (node (ref "U6") (pin "17") (pinfunction "PC2_17") (pintype "bidirectional"))
    )
    (net (code "303") (name "unconnected-(U6A-PC3-Pad18)") (class "Default")
      (node (ref "U6") (pin "18") (pinfunction "PC3_18") (pintype "bidirectional"))
    )
    (net (code "304") (name "unconnected-(U6A-PC5-Pad34)") (class "Default")
      (node (ref "U6") (pin "34") (pinfunction "PC5_34") (pintype "bidirectional"))
    )
    (net (code "305") (name "unconnected-(U6A-PC6-Pad63)") (class "Default")
      (node (ref "U6") (pin "63") (pinfunction "PC6_63") (pintype "bidirectional"))
    )
    (net (code "306") (name "unconnected-(U6A-PC7-Pad64)") (class "Default")
      (node (ref "U6") (pin "64") (pinfunction "PC7_64") (pintype "bidirectional"))
    )
    (net (code "307") (name "unconnected-(U6A-PD0-Pad81)") (class "Default")
      (node (ref "U6") (pin "81") (pinfunction "PD0_81") (pintype "bidirectional"))
    )
    (net (code "308") (name "unconnected-(U6A-PD1-Pad82)") (class "Default")
      (node (ref "U6") (pin "82") (pinfunction "PD1_82") (pintype "bidirectional"))
    )
    (net (code "309") (name "unconnected-(U6A-PD3-Pad84)") (class "Default")
      (node (ref "U6") (pin "84") (pinfunction "PD3_84") (pintype "bidirectional"))
    )
    (net (code "310") (name "unconnected-(U6A-PD4-Pad85)") (class "Default")
      (node (ref "U6") (pin "85") (pinfunction "PD4_85") (pintype "bidirectional"))
    )
    (net (code "311") (name "unconnected-(U6A-PD5-Pad86)") (class "Default")
      (node (ref "U6") (pin "86") (pinfunction "PD5_86") (pintype "bidirectional"))
    )
    (net (code "312") (name "unconnected-(U6A-PD6-Pad87)") (class "Default")
      (node (ref "U6") (pin "87") (pinfunction "PD6_87") (pintype "bidirectional"))
    )
    (net (code "313") (name "unconnected-(U6A-PD7-Pad88)") (class "Default")
      (node (ref "U6") (pin "88") (pinfunction "PD7_88") (pintype "bidirectional"))
    )
    (net (code "314") (name "unconnected-(U6A-PD13-Pad60)") (class "Default")
      (node (ref "U6") (pin "60") (pinfunction "PD13_60") (pintype "bidirectional"))
    )
    (net (code "315") (name "unconnected-(U6A-PD14-Pad61)") (class "Default")
      (node (ref "U6") (pin "61") (pinfunction "PD14_61") (pintype "bidirectional"))
    )
    (net (code "316") (name "unconnected-(U6A-PD15-Pad62)") (class "Default")
      (node (ref "U6") (pin "62") (pinfunction "PD15_62") (pintype "bidirectional"))
    )
    (net (code "317") (name "unconnected-(U6A-PE0-Pad97)") (class "Default")
      (node (ref "U6") (pin "97") (pinfunction "PE0_97") (pintype "bidirectional"))
    )
    (net (code "318") (name "unconnected-(U6A-PE1-Pad98)") (class "Default")
      (node (ref "U6") (pin "98") (pinfunction "PE1_98") (pintype "bidirectional"))
    )
    (net (code "319") (name "unconnected-(U6A-PE2-Pad1)") (class "Default")
      (node (ref "U6") (pin "1") (pinfunction "PE2_1") (pintype "bidirectional"))
    )
    (net (code "320") (name "unconnected-(U6A-PE3-Pad2)") (class "Default")
      (node (ref "U6") (pin "2") (pinfunction "PE3_2") (pintype "bidirectional"))
    )
    (net (code "321") (name "unconnected-(U6A-PE4-Pad3)") (class "Default")
      (node (ref "U6") (pin "3") (pinfunction "PE4_3") (pintype "bidirectional"))
    )
    (net (code "322") (name "unconnected-(U6A-PE5-Pad4)") (class "Default")
      (node (ref "U6") (pin "4") (pinfunction "PE5_4") (pintype "bidirectional"))
    )
    (net (code "323") (name "unconnected-(U6A-PE6-Pad5)") (class "Default")
      (node (ref "U6") (pin "5") (pinfunction "PE6_5") (pintype "bidirectional"))
    )
    (net (code "324") (name "unconnected-(U6A-PE11-Pad42)") (class "Default")
      (node (ref "U6") (pin "42") (pinfunction "PE11_42") (pintype "bidirectional"))
    )
    (net (code "325") (name "unconnected-(U6A-PE12-Pad43)") (class "Default")
      (node (ref "U6") (pin "43") (pinfunction "PE12_43") (pintype "bidirectional"))
    )
    (net (code "326") (name "unconnected-(U6A-PE13-Pad44)") (class "Default")
      (node (ref "U6") (pin "44") (pinfunction "PE13_44") (pintype "bidirectional"))
    )
    (net (code "327") (name "unconnected-(U6A-PE14-Pad45)") (class "Default")
      (node (ref "U6") (pin "45") (pinfunction "PE14_45") (pintype "bidirectional"))
    )
    (net (code "328") (name "unconnected-(U6A-PE15-Pad46)") (class "Default")
      (node (ref "U6") (pin "46") (pinfunction "PE15_46") (pintype "bidirectional"))
    )
    (net (code "329") (name "unconnected-(U6D-PA4-Pad29)") (class "Default")
      (node (ref "U6") (pin "29") (pinfunction "PA4_29") (pintype "bidirectional"))
    )
    (net (code "330") (name "unconnected-(U6D-PA5-Pad30)") (class "Default")
      (node (ref "U6") (pin "30") (pinfunction "PA5_30") (pintype "bidirectional"))
    )
    (net (code "331") (name "unconnected-(U6D-PA9-Pad68)") (class "Default")
      (node (ref "U6") (pin "68") (pinfunction "PA9_68") (pintype "bidirectional"))
    )
    (net (code "332") (name "unconnected-(U6D-PA10-Pad69)") (class "Default")
      (node (ref "U6") (pin "69") (pinfunction "PA10_69") (pintype "bidirectional"))
    )
    (net (code "333") (name "unconnected-(U6D-PA11-Pad70)") (class "Default")
      (node (ref "U6") (pin "70") (pinfunction "PA11_70") (pintype "bidirectional"))
    )
    (net (code "334") (name "unconnected-(U6D-PA12-Pad71)") (class "Default")
      (node (ref "U6") (pin "71") (pinfunction "PA12_71") (pintype "bidirectional"))
    )
    (net (code "335") (name "unconnected-(U6D-PB2-BOOT1-Pad37)") (class "Default")
      (node (ref "U6") (pin "37") (pinfunction "PB2-BOOT1_37") (pintype "bidirectional"))
    )
    (net (code "336") (name "unconnected-(U6D-PB3(JTDO{slash}TRACESWO)-Pad89)") (class "Default")
      (node (ref "U6") (pin "89") (pinfunction "PB3(JTDO/TRACESWO)_89") (pintype "bidirectional"))
    )
    (net (code "337") (name "unconnected-(U6D-PB4(NJTRST)-Pad90)") (class "Default")
      (node (ref "U6") (pin "90") (pinfunction "PB4(NJTRST)_90") (pintype "bidirectional"))
    )
    (net (code "338") (name "unconnected-(U6D-PB5-Pad91)") (class "Default")
      (node (ref "U6") (pin "91") (pinfunction "PB5_91") (pintype "bidirectional"))
    )
    (net (code "339") (name "unconnected-(U6D-PB12-Pad51)") (class "Default")
      (node (ref "U6") (pin "51") (pinfunction "PB12_51") (pintype "bidirectional"))
    )
    (net (code "340") (name "unconnected-(U6D-PB13-Pad52)") (class "Default")
      (node (ref "U6") (pin "52") (pinfunction "PB13_52") (pintype "bidirectional"))
    )
    (net (code "341") (name "unconnected-(U6D-PB14-Pad53)") (class "Default")
      (node (ref "U6") (pin "53") (pinfunction "PB14_53") (pintype "bidirectional"))
    )
    (net (code "342") (name "unconnected-(U6D-PB15-Pad54)") (class "Default")
      (node (ref "U6") (pin "54") (pinfunction "PB15_54") (pintype "bidirectional"))
    )
    (net (code "343") (name "unconnected-(U6D-PC4-Pad33)") (class "Default")
      (node (ref "U6") (pin "33") (pinfunction "PC4_33") (pintype "bidirectional"))
    )
    (net (code "344") (name "unconnected-(U6D-PC9-Pad66)") (class "Default")
      (node (ref "U6") (pin "66") (pinfunction "PC9_66") (pintype "bidirectional"))
    )
    (net (code "345") (name "unconnected-(U6D-PC10-Pad78)") (class "Default")
      (node (ref "U6") (pin "78") (pinfunction "PC10_78") (pintype "bidirectional"))
    )
    (net (code "346") (name "unconnected-(U6D-PC11-Pad79)") (class "Default")
      (node (ref "U6") (pin "79") (pinfunction "PC11_79") (pintype "bidirectional"))
    )
    (net (code "347") (name "unconnected-(U6D-PC12-Pad80)") (class "Default")
      (node (ref "U6") (pin "80") (pinfunction "PC12_80") (pintype "bidirectional"))
    )
    (net (code "348") (name "unconnected-(U6D-PC13-Pad7)") (class "Default")
      (node (ref "U6") (pin "7") (pinfunction "PC13_7") (pintype "bidirectional"))
    )
    (net (code "349") (name "unconnected-(U6D-PD8-Pad55)") (class "Default")
      (node (ref "U6") (pin "55") (pinfunction "PD8_55") (pintype "bidirectional"))
    )
    (net (code "350") (name "unconnected-(U6D-PD9-Pad56)") (class "Default")
      (node (ref "U6") (pin "56") (pinfunction "PD9_56") (pintype "bidirectional"))
    )
    (net (code "351") (name "unconnected-(U6D-PD10-Pad57)") (class "Default")
      (node (ref "U6") (pin "57") (pinfunction "PD10_57") (pintype "bidirectional"))
    )
    (net (code "352") (name "unconnected-(U6D-PD11-Pad58)") (class "Default")
      (node (ref "U6") (pin "58") (pinfunction "PD11_58") (pintype "bidirectional"))
    )
    (net (code "353") (name "unconnected-(U6D-PD12-Pad59)") (class "Default")
      (node (ref "U6") (pin "59") (pinfunction "PD12_59") (pintype "bidirectional"))
    )
    (net (code "354") (name "unconnected-(U6D-PE9-Pad40)") (class "Default")
      (node (ref "U6") (pin "40") (pinfunction "PE9_40") (pintype "bidirectional+no_connect"))
    )
    (net (code "355") (name "unconnected-(U6D-PE10-Pad41)") (class "Default")
      (node (ref "U6") (pin "41") (pinfunction "PE10_41") (pintype "bidirectional+no_connect"))
    )
  )
)
